# CONTROL_485.net
KiCad netlist of a schematic drawn in Altium Designer
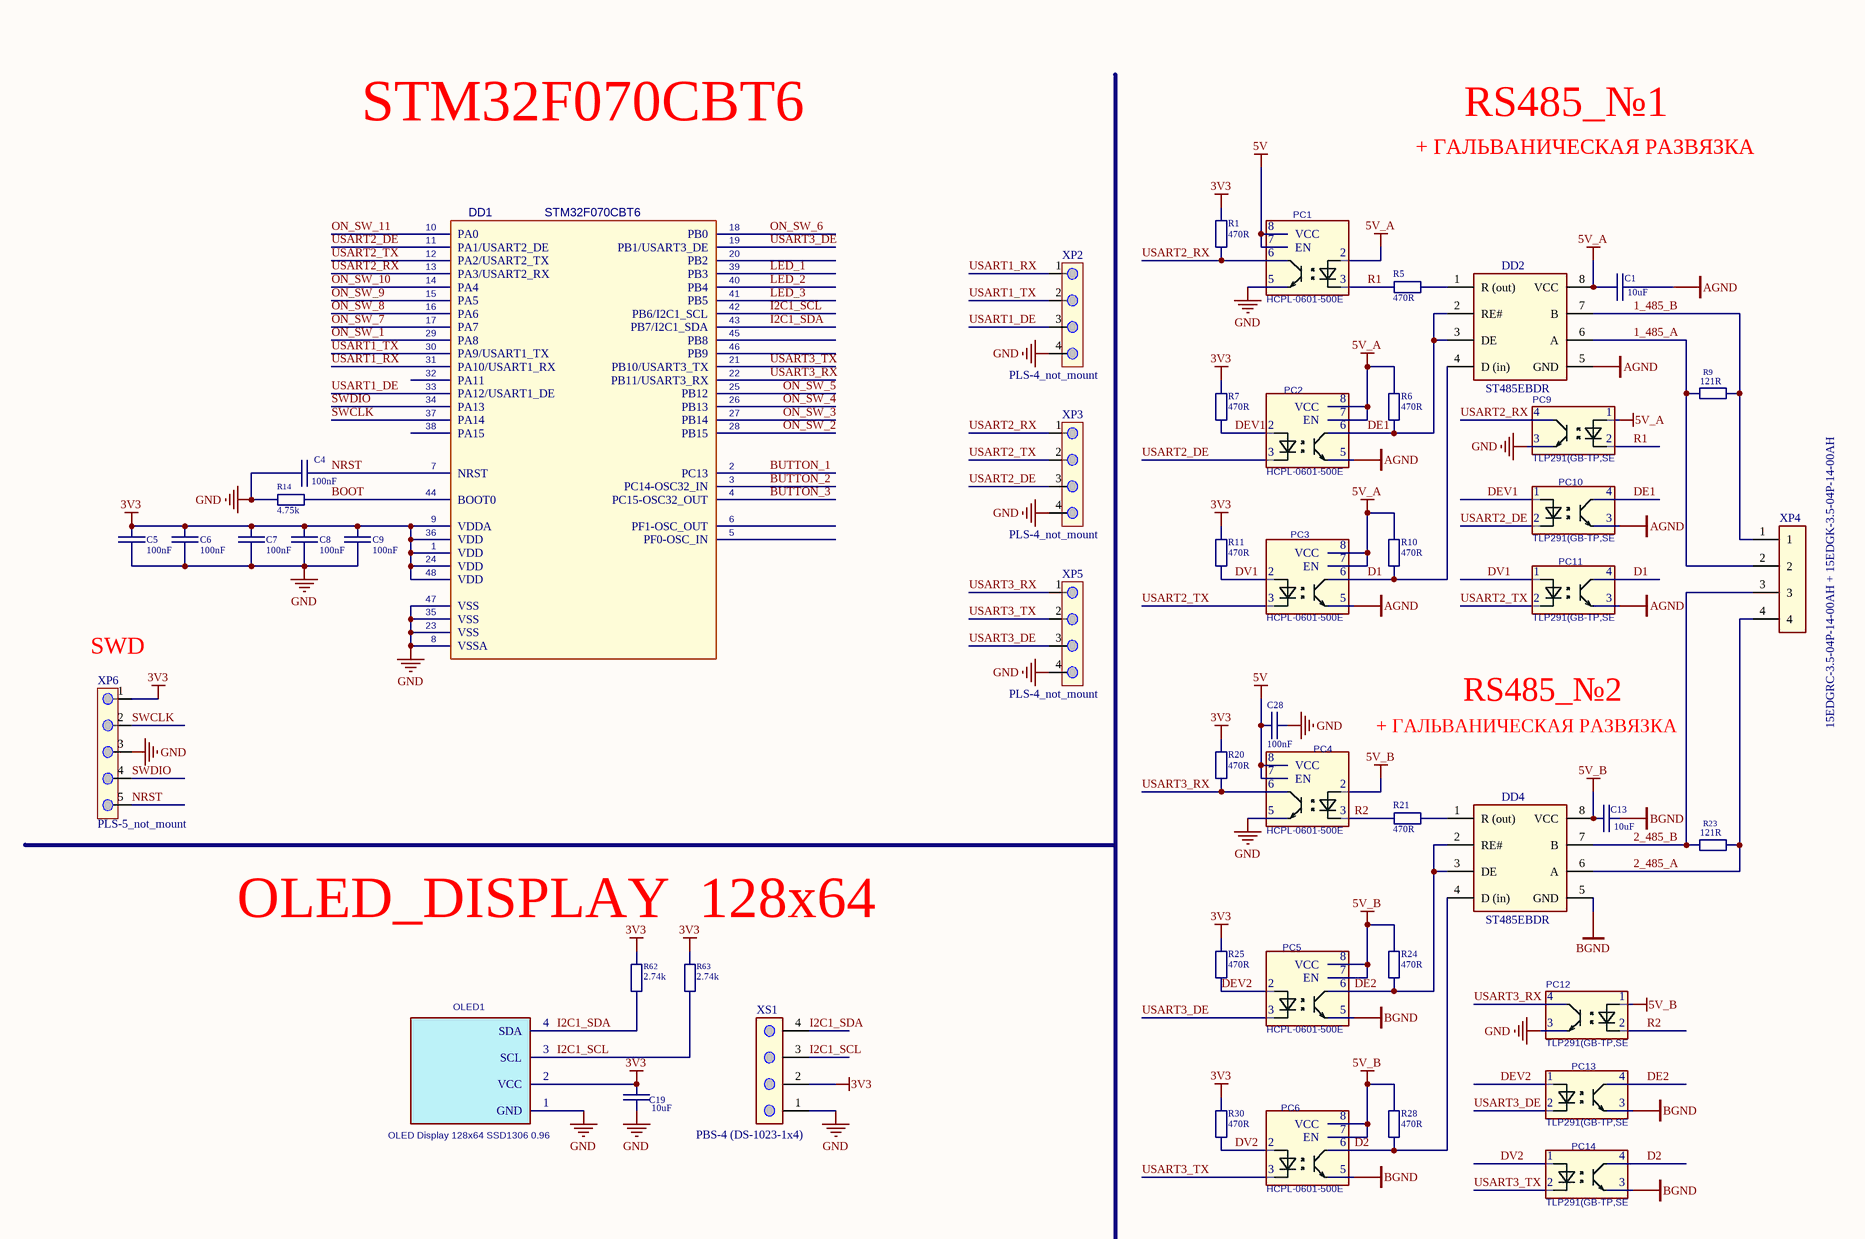
[diagram p0: CONTROL_485.SchDoc, top left]
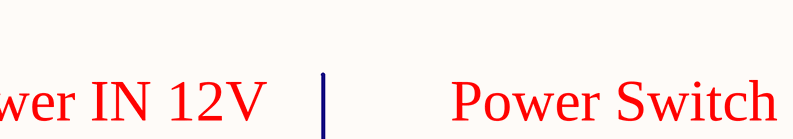
[diagram p1: CONTROL_485.SchDoc, top right]
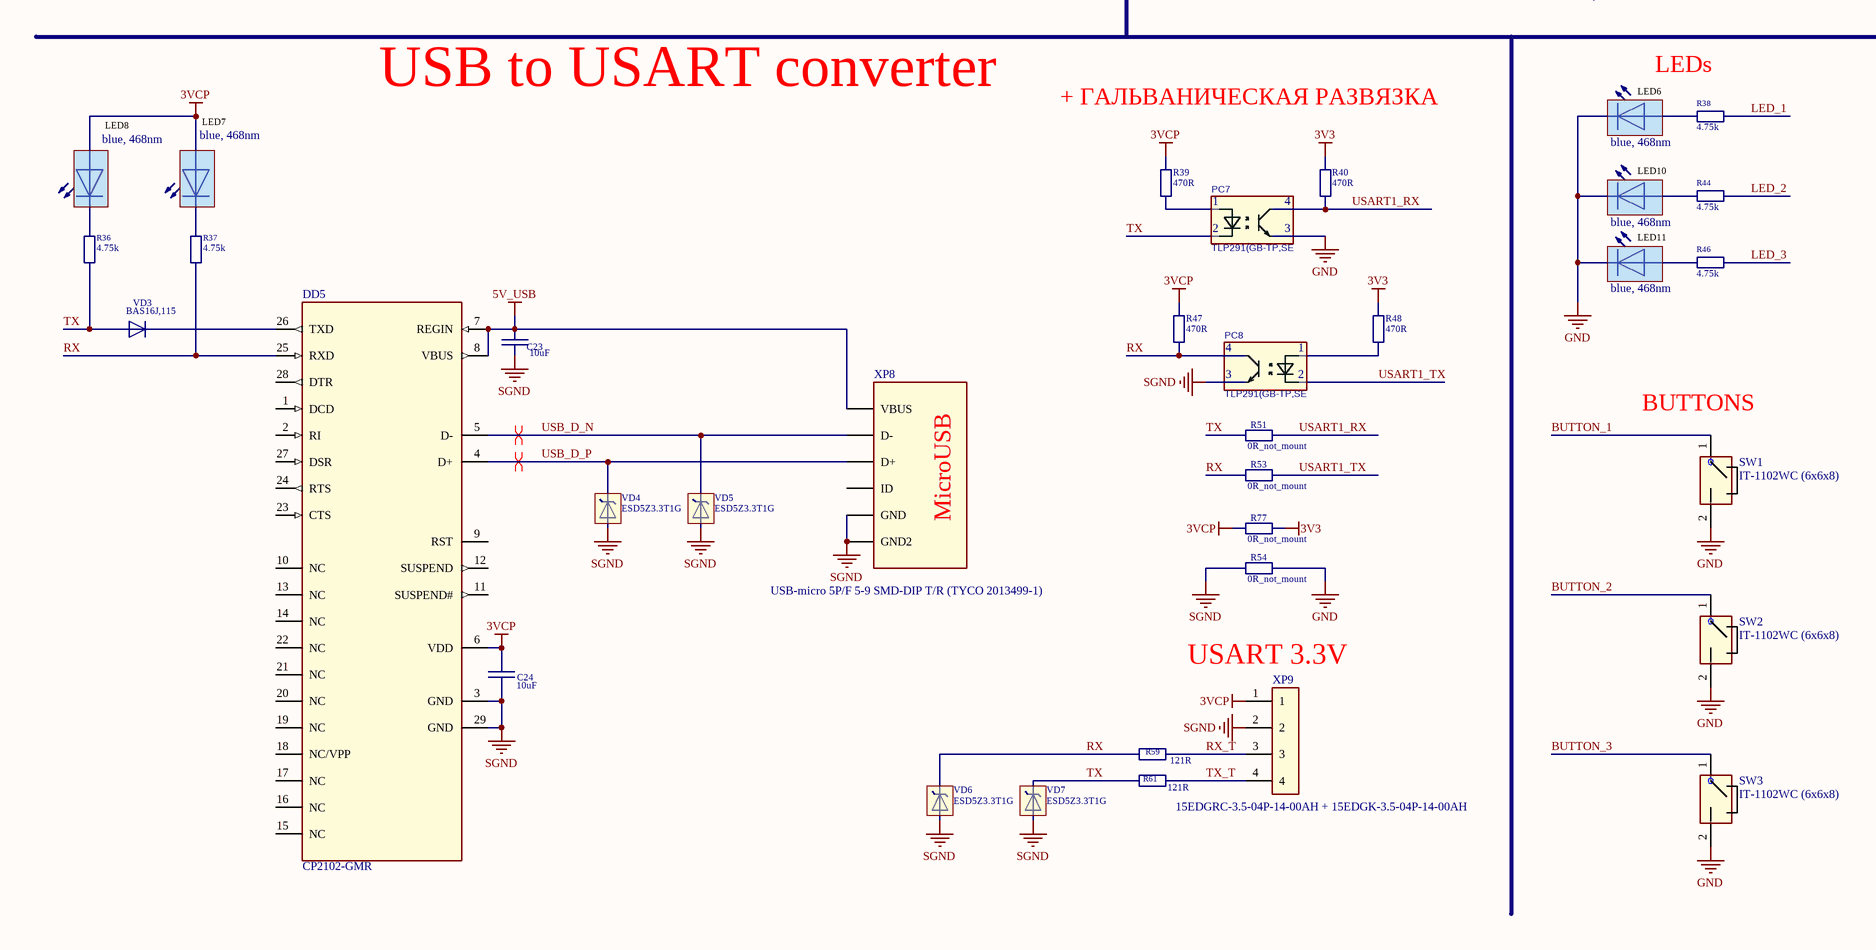
[diagram p2: CONTROL_485.SchDoc, bottom left]
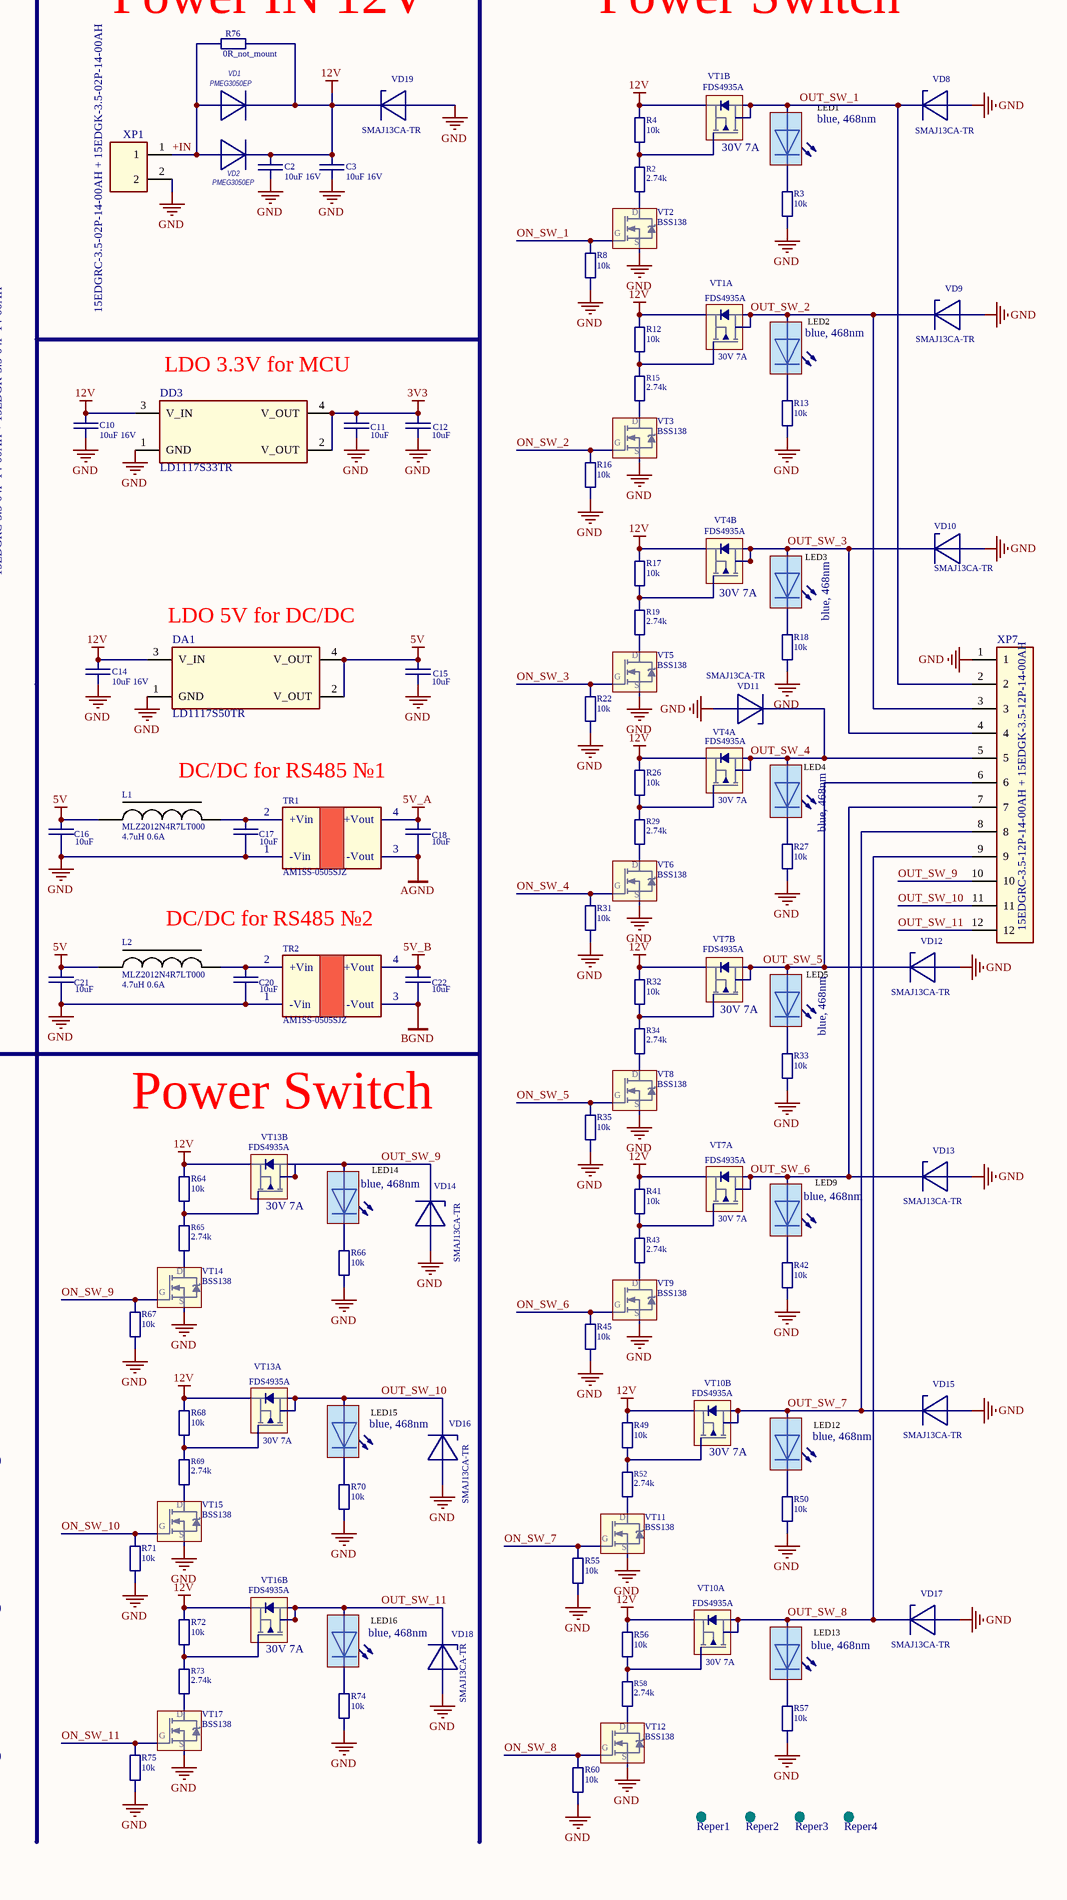
[diagram p3: CONTROL_485.SchDoc, bottom right]

(export (version "E")
  (design (tool "Eeschema 10.0.6"))
  (components
    (comp (ref "C1")
      (value "C0805, 10uF, 10V, X5R")
      (footprint "C0805")
      (fields (field (name "CAPACITANCE") "10uF"))
      (libsource (lib "CAPACITORS") (part "C0805, 10uF, 10V, X5R"))
    )
    (comp (ref "C2")
      (value "C0805, 10uF, 16V, X5R")
      (footprint "C0805")
      (fields (field (name "CAPACITANCE") "10uF 16V"))
      (libsource (lib "*") (part "C0805, 10uF, 16V, X5R"))
    )
    (comp (ref "C3")
      (value "C0805, 10uF, 16V, X5R")
      (footprint "C0805")
      (fields (field (name "CAPACITANCE") "10uF 16V"))
      (libsource (lib "*") (part "C0805, 10uF, 16V, X5R"))
    )
    (comp (ref "C4")
      (value "C0603, 100nF 50V")
      (footprint "C0603")
      (fields (field (name "CAPACITANCE") "100nF"))
      (libsource (lib "CAPACITORS") (part "C0603, 100nF 50V"))
    )
    (comp (ref "C5")
      (value "C0603, 100nF 50V")
      (footprint "C0603")
      (fields (field (name "CAPACITANCE") "100nF"))
      (libsource (lib "CAPACITORS") (part "C0603, 100nF 50V"))
    )
    (comp (ref "C6")
      (value "C0603, 100nF 50V")
      (footprint "C0603")
      (fields (field (name "CAPACITANCE") "100nF"))
      (libsource (lib "CAPACITORS") (part "C0603, 100nF 50V"))
    )
    (comp (ref "C7")
      (value "C0603, 100nF 50V")
      (footprint "C0603")
      (fields (field (name "CAPACITANCE") "100nF"))
      (libsource (lib "CAPACITORS") (part "C0603, 100nF 50V"))
    )
    (comp (ref "C8")
      (value "C0603, 100nF 50V")
      (footprint "C0603")
      (fields (field (name "CAPACITANCE") "100nF"))
      (libsource (lib "CAPACITORS") (part "C0603, 100nF 50V"))
    )
    (comp (ref "C9")
      (value "C0603, 100nF 50V")
      (footprint "C0603")
      (fields (field (name "CAPACITANCE") "100nF"))
      (libsource (lib "CAPACITORS") (part "C0603, 100nF 50V"))
    )
    (comp (ref "C10")
      (value "C0805, 10uF, 16V, X5R")
      (footprint "C0805")
      (fields (field (name "CAPACITANCE") "10uF 16V"))
      (libsource (lib "*") (part "C0805, 10uF, 16V, X5R"))
    )
    (comp (ref "C11")
      (value "C0805, 10uF, 10V, X5R")
      (footprint "C0805")
      (fields (field (name "CAPACITANCE") "10uF"))
      (libsource (lib "CAPACITORS") (part "C0805, 10uF, 10V, X5R"))
    )
    (comp (ref "C12")
      (value "C0805, 10uF, 10V, X5R")
      (footprint "C0805")
      (fields (field (name "CAPACITANCE") "10uF"))
      (libsource (lib "CAPACITORS") (part "C0805, 10uF, 10V, X5R"))
    )
    (comp (ref "C13")
      (value "C0805, 10uF, 10V, X5R")
      (footprint "C0805")
      (fields (field (name "CAPACITANCE") "10uF"))
      (libsource (lib "CAPACITORS") (part "C0805, 10uF, 10V, X5R"))
    )
    (comp (ref "C14")
      (value "C0805, 10uF, 16V, X5R")
      (footprint "C0805")
      (fields (field (name "CAPACITANCE") "10uF 16V"))
      (libsource (lib "*") (part "C0805, 10uF, 16V, X5R"))
    )
    (comp (ref "C15")
      (value "C0805, 10uF, 10V, X5R")
      (footprint "C0805")
      (fields (field (name "CAPACITANCE") "10uF"))
      (libsource (lib "CAPACITORS") (part "C0805, 10uF, 10V, X5R"))
    )
    (comp (ref "C16")
      (value "C0805, 10uF, 10V, X5R")
      (footprint "C0805")
      (fields (field (name "CAPACITANCE") "10uF"))
      (libsource (lib "CAPACITORS") (part "C0805, 10uF, 10V, X5R"))
    )
    (comp (ref "C17")
      (value "C0805, 10uF, 10V, X5R")
      (footprint "C0805")
      (fields (field (name "CAPACITANCE") "10uF"))
      (libsource (lib "CAPACITORS") (part "C0805, 10uF, 10V, X5R"))
    )
    (comp (ref "C18")
      (value "C0805, 10uF, 10V, X5R")
      (footprint "C0805")
      (fields (field (name "CAPACITANCE") "10uF"))
      (libsource (lib "CAPACITORS") (part "C0805, 10uF, 10V, X5R"))
    )
    (comp (ref "C19")
      (value "C0805, 10uF, 10V, X5R")
      (footprint "C0805")
      (fields (field (name "CAPACITANCE") "10uF"))
      (libsource (lib "CAPACITORS") (part "C0805, 10uF, 10V, X5R"))
    )
    (comp (ref "C20")
      (value "C0805, 10uF, 10V, X5R")
      (footprint "C0805")
      (fields (field (name "CAPACITANCE") "10uF"))
      (libsource (lib "CAPACITORS") (part "C0805, 10uF, 10V, X5R"))
    )
    (comp (ref "C21")
      (value "C0805, 10uF, 10V, X5R")
      (footprint "C0805")
      (fields (field (name "CAPACITANCE") "10uF"))
      (libsource (lib "CAPACITORS") (part "C0805, 10uF, 10V, X5R"))
    )
    (comp (ref "C22")
      (value "C0805, 10uF, 10V, X5R")
      (footprint "C0805")
      (fields (field (name "CAPACITANCE") "10uF"))
      (libsource (lib "CAPACITORS") (part "C0805, 10uF, 10V, X5R"))
    )
    (comp (ref "C23")
      (value "C0805, 10uF, 10V, X5R")
      (footprint "C0805")
      (fields (field (name "CAPACITANCE") "10uF"))
      (libsource (lib "CAPACITORS") (part "C0805, 10uF, 10V, X5R"))
    )
    (comp (ref "C24")
      (value "C0805, 10uF, 10V, X5R")
      (footprint "C0805")
      (fields (field (name "CAPACITANCE") "10uF"))
      (libsource (lib "CAPACITORS") (part "C0805, 10uF, 10V, X5R"))
    )
    (comp (ref "C28")
      (value "C0603, 100nF 50V")
      (footprint "C0603")
      (fields (field (name "CAPACITANCE") "100nF"))
      (libsource (lib "CAPACITORS") (part "C0603, 100nF 50V"))
    )
    (comp (ref "DA1")
      (value "LD1117S50TR")
      (footprint "SOT223_N")
      (description "IC REG LDO 0.8A 5V SOT223-4")
      (fields
        (field (name "MANUFACTURER PART NUMBER") "NX1117C33Z,115")
        (field (name "MANUFACTURER") "NXP Semiconductors")
      )
      (libsource (lib "DIGITAL and ANALOG ICs") (part "LD1117S50TR"))
    )
    (comp (ref "DD1")
      (value "STM32F070CBT6")
      (footprint "LQFP48_L")
      (description "ARM® Cortex®-M0 STM32F0 Microcontroller IC 32-Bit 48MHz 128KB (128K x 8) FLASH 48-LQFP (7x7)")
      (libsource (lib "*") (part "STM32F070CBT6"))
    )
    (comp (ref "DD2")
      (value "ST485EBDR")
      (footprint "SO-8_L")
      (description "Transceiver RS485, 8-SOIC")
      (libsource (lib "*") (part "ST485EBDR"))
    )
    (comp (ref "DD3")
      (value "LD1117S33TR")
      (footprint "SOT223_N")
      (description "IC REG LDO 0.8A 3.3V SOT223-4")
      (fields
        (field (name "MANUFACTURER PART NUMBER") "NX1117C33Z,115")
        (field (name "MANUFACTURER") "NXP Semiconductors")
      )
      (libsource (lib "DIGITAL and ANALOG ICs") (part "LD1117S33TR"))
    )
    (comp (ref "DD4")
      (value "ST485EBDR")
      (footprint "SO-8_L")
      (description "Transceiver RS485, 8-SOIC")
      (libsource (lib "*") (part "ST485EBDR"))
    )
    (comp (ref "DD5")
      (value "CP2102-GMR")
      (footprint "QFN28")
      (description "IC USB-TO-UART BRIDGE 28VQFN")
      (libsource (lib "DIGITAL and ANALOG ICs") (part "CP2102-GMR"))
    )
    (comp (ref "L1")
      (value "MLZ2012N4R7LT000")
      (footprint "L0805")
      (description "4.7µH Shielded Multilayer Inductor 600mA 180mOhm 0805 (2012 Metric)")
      (fields (field (name "ALTIUM_UNNAMED_1") "4.7uH 0.6A"))
      (libsource (lib "INDUCTORS") (part "MLZ2012N4R7LT000"))
    )
    (comp (ref "L2")
      (value "MLZ2012N4R7LT000")
      (footprint "L0805")
      (description "4.7µH Shielded Multilayer Inductor 600mA 180mOhm 0805 (2012 Metric)")
      (fields (field (name "ALTIUM_UNNAMED_1") "4.7uH 0.6A"))
      (libsource (lib "INDUCTORS") (part "MLZ2012N4R7LT000"))
    )
    (comp (ref "LED1")
      (value "FYLS-0805BUBC")
      (footprint "LED_0805_B")
      (description "LED, blue, 0805")
      (fields (field (name "ALTIUM_UNNAMED_1") "blue, 468nm"))
      (libsource (lib "AltiumDesignLibrary") (part "FYLS-0805BUBC"))
    )
    (comp (ref "LED2")
      (value "FYLS-0805BUBC")
      (footprint "LED_0805_B")
      (description "LED, blue, 0805")
      (fields (field (name "ALTIUM_UNNAMED_1") "blue, 468nm"))
      (libsource (lib "AltiumDesignLibrary") (part "FYLS-0805BUBC"))
    )
    (comp (ref "LED3")
      (value "FYLS-0805BUBC")
      (footprint "LED_0805_B")
      (description "LED, blue, 0805")
      (fields (field (name "ALTIUM_UNNAMED_1") "blue, 468nm"))
      (libsource (lib "AltiumDesignLibrary") (part "FYLS-0805BUBC"))
    )
    (comp (ref "LED4")
      (value "FYLS-0805BUBC")
      (footprint "LED_0805_B")
      (description "LED, blue, 0805")
      (fields (field (name "ALTIUM_UNNAMED_1") "blue, 468nm"))
      (libsource (lib "AltiumDesignLibrary") (part "FYLS-0805BUBC"))
    )
    (comp (ref "LED5")
      (value "FYLS-0805BUBC")
      (footprint "LED_0805_B")
      (description "LED, blue, 0805")
      (fields (field (name "ALTIUM_UNNAMED_1") "blue, 468nm"))
      (libsource (lib "AltiumDesignLibrary") (part "FYLS-0805BUBC"))
    )
    (comp (ref "LED6")
      (value "FYLS-0805BUBC")
      (footprint "LED_0805_B")
      (description "LED, blue, 0805")
      (fields (field (name "ALTIUM_UNNAMED_1") "blue, 468nm"))
      (libsource (lib "AltiumDesignLibrary") (part "FYLS-0805BUBC"))
    )
    (comp (ref "LED7")
      (value "FYLS-0805BUBC")
      (footprint "LED_0805_B")
      (description "LED, blue, 0805")
      (fields (field (name "ALTIUM_UNNAMED_1") "blue, 468nm"))
      (libsource (lib "") (part "FYLS-0805BUBC_1"))
    )
    (comp (ref "LED8")
      (value "FYLS-0805BUBC")
      (footprint "LED_0805_B")
      (description "LED, blue, 0805")
      (fields (field (name "ALTIUM_UNNAMED_1") "blue, 468nm"))
      (libsource (lib "") (part "FYLS-0805BUBC_1"))
    )
    (comp (ref "LED9")
      (value "FYLS-0805BUBC")
      (footprint "LED_0805_B")
      (description "LED, blue, 0805")
      (fields (field (name "ALTIUM_UNNAMED_1") "blue, 468nm"))
      (libsource (lib "AltiumDesignLibrary") (part "FYLS-0805BUBC"))
    )
    (comp (ref "LED10")
      (value "FYLS-0805BUBC")
      (footprint "LED_0805_B")
      (description "LED, blue, 0805")
      (fields (field (name "ALTIUM_UNNAMED_1") "blue, 468nm"))
      (libsource (lib "AltiumDesignLibrary") (part "FYLS-0805BUBC"))
    )
    (comp (ref "LED11")
      (value "FYLS-0805BUBC")
      (footprint "LED_0805_B")
      (description "LED, blue, 0805")
      (fields (field (name "ALTIUM_UNNAMED_1") "blue, 468nm"))
      (libsource (lib "AltiumDesignLibrary") (part "FYLS-0805BUBC"))
    )
    (comp (ref "LED12")
      (value "FYLS-0805BUBC")
      (footprint "LED_0805_B")
      (description "LED, blue, 0805")
      (fields (field (name "ALTIUM_UNNAMED_1") "blue, 468nm"))
      (libsource (lib "AltiumDesignLibrary") (part "FYLS-0805BUBC"))
    )
    (comp (ref "LED13")
      (value "FYLS-0805BUBC")
      (footprint "LED_0805_B")
      (description "LED, blue, 0805")
      (fields (field (name "ALTIUM_UNNAMED_1") "blue, 468nm"))
      (libsource (lib "AltiumDesignLibrary") (part "FYLS-0805BUBC"))
    )
    (comp (ref "LED14")
      (value "FYLS-0805BUBC")
      (footprint "LED_0805_B")
      (description "LED, blue, 0805")
      (fields (field (name "ALTIUM_UNNAMED_1") "blue, 468nm"))
      (libsource (lib "AltiumDesignLibrary") (part "FYLS-0805BUBC"))
    )
    (comp (ref "LED15")
      (value "FYLS-0805BUBC")
      (footprint "LED_0805_B")
      (description "LED, blue, 0805")
      (fields (field (name "ALTIUM_UNNAMED_1") "blue, 468nm"))
      (libsource (lib "AltiumDesignLibrary") (part "FYLS-0805BUBC"))
    )
    (comp (ref "LED16")
      (value "FYLS-0805BUBC")
      (footprint "LED_0805_B")
      (description "LED, blue, 0805")
      (fields (field (name "ALTIUM_UNNAMED_1") "blue, 468nm"))
      (libsource (lib "AltiumDesignLibrary") (part "FYLS-0805BUBC"))
    )
    (comp (ref "OLED1")
      (value "OLED Display 128x64 SSD1306 0.96")
      (footprint "OLED Display 128x64 SSD1306 0.96")
      (libsource (lib "LED") (part "OLED Display 128x64 SSD1306 0.96"))
    )
    (comp (ref "PC1")
      (value "HCPL-0601-500E")
      (footprint "SO-8_HCPL")
      (description "OPTOISO 3.75KV OPN COLLECTOR 8SO")
      (libsource (lib "") (part "HCPL-0601-500E_1"))
    )
    (comp (ref "PC2")
      (value "HCPL-0601-500E")
      (footprint "SO-8_HCPL")
      (description "OPTOISO 3.75KV OPN COLLECTOR 8SO")
      (libsource (lib "LED") (part "HCPL-0601-500E"))
    )
    (comp (ref "PC3")
      (value "HCPL-0601-500E")
      (footprint "SO-8_HCPL")
      (description "OPTOISO 3.75KV OPN COLLECTOR 8SO")
      (libsource (lib "LED") (part "HCPL-0601-500E"))
    )
    (comp (ref "PC4")
      (value "HCPL-0601-500E")
      (footprint "SO-8_HCPL")
      (description "OPTOISO 3.75KV OPN COLLECTOR 8SO")
      (libsource (lib "") (part "HCPL-0601-500E_1"))
    )
    (comp (ref "PC5")
      (value "HCPL-0601-500E")
      (footprint "SO-8_HCPL")
      (description "OPTOISO 3.75KV OPN COLLECTOR 8SO")
      (libsource (lib "LED") (part "HCPL-0601-500E"))
    )
    (comp (ref "PC6")
      (value "HCPL-0601-500E")
      (footprint "SO-8_HCPL")
      (description "OPTOISO 3.75KV OPN COLLECTOR 8SO")
      (libsource (lib "LED") (part "HCPL-0601-500E"))
    )
    (comp (ref "PC7")
      (value "TLP291(GB-TP,SE")
      (footprint "TLP292")
      (description "Photocoupler TLP291")
      (libsource (lib "*") (part "TLP291(GB-TP,SE"))
    )
    (comp (ref "PC8")
      (value "TLP291(GB-TP,SE")
      (footprint "TLP292")
      (description "Photocoupler TLP291")
      (libsource (lib "") (part "TLP291(GB-TP,SE_1"))
    )
    (comp (ref "PC9")
      (value "TLP291(GB-TP,SE")
      (footprint "TLP292")
      (description "Photocoupler TLP291")
      (libsource (lib "") (part "TLP291(GB-TP,SE_1"))
    )
    (comp (ref "PC10")
      (value "TLP291(GB-TP,SE")
      (footprint "TLP292")
      (description "Photocoupler TLP291")
      (libsource (lib "LED") (part "TLP291(GB-TP,SE"))
    )
    (comp (ref "PC11")
      (value "TLP291(GB-TP,SE")
      (footprint "TLP292")
      (description "Photocoupler TLP291")
      (libsource (lib "LED") (part "TLP291(GB-TP,SE"))
    )
    (comp (ref "PC12")
      (value "TLP291(GB-TP,SE")
      (footprint "TLP292")
      (description "Photocoupler TLP291")
      (libsource (lib "") (part "TLP291(GB-TP,SE_1"))
    )
    (comp (ref "PC13")
      (value "TLP291(GB-TP,SE")
      (footprint "TLP292")
      (description "Photocoupler TLP291")
      (libsource (lib "LED") (part "TLP291(GB-TP,SE"))
    )
    (comp (ref "PC14")
      (value "TLP291(GB-TP,SE")
      (footprint "TLP292")
      (description "Photocoupler TLP291")
      (libsource (lib "LED") (part "TLP291(GB-TP,SE"))
    )
    (comp (ref "R1")
      (value "R0603, 470R 1%")
      (footprint "R0603")
      (fields (field (name "ALTIUM_UNNAMED_1") "470R"))
      (libsource (lib "RESISTOR") (part "R0603, 470R 1%"))
    )
    (comp (ref "R2")
      (value "R0603, 2.74k 1%")
      (footprint "R0603")
      (fields (field (name "RESISTANCE") "2.74k"))
      (libsource (lib "RESISTOR") (part "R0603, 2.74k 1%"))
    )
    (comp (ref "R3")
      (value "R0603, 10k 1%")
      (footprint "R0603")
      (fields (field (name "RESISTANCE") "10k"))
      (libsource (lib "*") (part "R0603, 10k 1%"))
    )
    (comp (ref "R4")
      (value "R0603, 10k 1%")
      (footprint "R0603")
      (fields (field (name "RESISTANCE") "10k"))
      (libsource (lib "*") (part "R0603, 10k 1%"))
    )
    (comp (ref "R5")
      (value "R0603, 470R 1%")
      (footprint "R0603")
      (fields (field (name "ALTIUM_UNNAMED_1") "470R"))
      (libsource (lib "RESISTOR") (part "R0603, 470R 1%"))
    )
    (comp (ref "R6")
      (value "R0603, 470R 1%")
      (footprint "R0603")
      (fields (field (name "ALTIUM_UNNAMED_1") "470R"))
      (libsource (lib "RESISTOR") (part "R0603, 470R 1%"))
    )
    (comp (ref "R7")
      (value "R0603, 470R 1%")
      (footprint "R0603")
      (fields (field (name "ALTIUM_UNNAMED_1") "470R"))
      (libsource (lib "RESISTOR") (part "R0603, 470R 1%"))
    )
    (comp (ref "R8")
      (value "R0603, 10k 1%")
      (footprint "R0603")
      (fields (field (name "RESISTANCE") "10k"))
      (libsource (lib "*") (part "R0603, 10k 1%"))
    )
    (comp (ref "R9")
      (value "R0603, 121R 1%")
      (footprint "R0603")
      (fields (field (name "RESISTANCE") "121R"))
      (libsource (lib "MAIN_BOARD_V3") (part "R0603, 121R 1%"))
    )
    (comp (ref "R10")
      (value "R0603, 470R 1%")
      (footprint "R0603")
      (fields (field (name "ALTIUM_UNNAMED_1") "470R"))
      (libsource (lib "RESISTOR") (part "R0603, 470R 1%"))
    )
    (comp (ref "R11")
      (value "R0603, 470R 1%")
      (footprint "R0603")
      (fields (field (name "ALTIUM_UNNAMED_1") "470R"))
      (libsource (lib "RESISTOR") (part "R0603, 470R 1%"))
    )
    (comp (ref "R12")
      (value "R0603, 10k 1%")
      (footprint "R0603")
      (fields (field (name "RESISTANCE") "10k"))
      (libsource (lib "RESISTOR") (part "R0603, 10k 1%"))
    )
    (comp (ref "R13")
      (value "R0603, 10k 1%")
      (footprint "R0603")
      (fields (field (name "RESISTANCE") "10k"))
      (libsource (lib "*") (part "R0603, 10k 1%"))
    )
    (comp (ref "R14")
      (value "R0603, 4.75k 1%")
      (footprint "R0603")
      (fields (field (name "RESISTANCE") "4.75k"))
      (libsource (lib "RESISTOR") (part "R0603, 4.75k 1%"))
    )
    (comp (ref "R15")
      (value "R0603, 2.74k 1%")
      (footprint "R0603")
      (fields (field (name "RESISTANCE") "2.74k"))
      (libsource (lib "RESISTOR") (part "R0603, 2.74k 1%"))
    )
    (comp (ref "R16")
      (value "R0603, 10k 1%")
      (footprint "R0603")
      (fields (field (name "RESISTANCE") "10k"))
      (libsource (lib "RESISTOR") (part "R0603, 10k 1%"))
    )
    (comp (ref "R17")
      (value "R0603, 10k 1%")
      (footprint "R0603")
      (fields (field (name "RESISTANCE") "10k"))
      (libsource (lib "RESISTOR") (part "R0603, 10k 1%"))
    )
    (comp (ref "R18")
      (value "R0603, 10k 1%")
      (footprint "R0603")
      (fields (field (name "RESISTANCE") "10k"))
      (libsource (lib "*") (part "R0603, 10k 1%"))
    )
    (comp (ref "R19")
      (value "R0603, 2.74k 1%")
      (footprint "R0603")
      (fields (field (name "RESISTANCE") "2.74k"))
      (libsource (lib "RESISTOR") (part "R0603, 2.74k 1%"))
    )
    (comp (ref "R20")
      (value "R0603, 470R 1%")
      (footprint "R0603")
      (fields (field (name "ALTIUM_UNNAMED_1") "470R"))
      (libsource (lib "RESISTOR") (part "R0603, 470R 1%"))
    )
    (comp (ref "R21")
      (value "R0603, 470R 1%")
      (footprint "R0603")
      (fields (field (name "ALTIUM_UNNAMED_1") "470R"))
      (libsource (lib "RESISTOR") (part "R0603, 470R 1%"))
    )
    (comp (ref "R22")
      (value "R0603, 10k 1%")
      (footprint "R0603")
      (fields (field (name "RESISTANCE") "10k"))
      (libsource (lib "RESISTOR") (part "R0603, 10k 1%"))
    )
    (comp (ref "R23")
      (value "R0603, 121R 1%")
      (footprint "R0603")
      (fields (field (name "RESISTANCE") "121R"))
      (libsource (lib "MAIN_BOARD_V3") (part "R0603, 121R 1%"))
    )
    (comp (ref "R24")
      (value "R0603, 470R 1%")
      (footprint "R0603")
      (fields (field (name "ALTIUM_UNNAMED_1") "470R"))
      (libsource (lib "RESISTOR") (part "R0603, 470R 1%"))
    )
    (comp (ref "R25")
      (value "R0603, 470R 1%")
      (footprint "R0603")
      (fields (field (name "ALTIUM_UNNAMED_1") "470R"))
      (libsource (lib "RESISTOR") (part "R0603, 470R 1%"))
    )
    (comp (ref "R26")
      (value "R0603, 10k 1%")
      (footprint "R0603")
      (fields (field (name "RESISTANCE") "10k"))
      (libsource (lib "RESISTOR") (part "R0603, 10k 1%"))
    )
    (comp (ref "R27")
      (value "R0603, 10k 1%")
      (footprint "R0603")
      (fields (field (name "RESISTANCE") "10k"))
      (libsource (lib "*") (part "R0603, 10k 1%"))
    )
    (comp (ref "R28")
      (value "R0603, 470R 1%")
      (footprint "R0603")
      (fields (field (name "ALTIUM_UNNAMED_1") "470R"))
      (libsource (lib "RESISTOR") (part "R0603, 470R 1%"))
    )
    (comp (ref "R29")
      (value "R0603, 2.74k 1%")
      (footprint "R0603")
      (fields (field (name "RESISTANCE") "2.74k"))
      (libsource (lib "RESISTOR") (part "R0603, 2.74k 1%"))
    )
    (comp (ref "R30")
      (value "R0603, 470R 1%")
      (footprint "R0603")
      (fields (field (name "ALTIUM_UNNAMED_1") "470R"))
      (libsource (lib "RESISTOR") (part "R0603, 470R 1%"))
    )
    (comp (ref "R31")
      (value "R0603, 10k 1%")
      (footprint "R0603")
      (fields (field (name "RESISTANCE") "10k"))
      (libsource (lib "RESISTOR") (part "R0603, 10k 1%"))
    )
    (comp (ref "R32")
      (value "R0603, 10k 1%")
      (footprint "R0603")
      (fields (field (name "RESISTANCE") "10k"))
      (libsource (lib "RESISTOR") (part "R0603, 10k 1%"))
    )
    (comp (ref "R33")
      (value "R0603, 10k 1%")
      (footprint "R0603")
      (fields (field (name "RESISTANCE") "10k"))
      (libsource (lib "*") (part "R0603, 10k 1%"))
    )
    (comp (ref "R34")
      (value "R0603, 2.74k 1%")
      (footprint "R0603")
      (fields (field (name "RESISTANCE") "2.74k"))
      (libsource (lib "RESISTOR") (part "R0603, 2.74k 1%"))
    )
    (comp (ref "R35")
      (value "R0603, 10k 1%")
      (footprint "R0603")
      (fields (field (name "RESISTANCE") "10k"))
      (libsource (lib "RESISTOR") (part "R0603, 10k 1%"))
    )
    (comp (ref "R36")
      (value "R0603, 4.75k 1%")
      (footprint "R0603")
      (fields (field (name "RESISTANCE") "4.75k"))
      (libsource (lib "RESISTOR") (part "R0603, 4.75k 1%"))
    )
    (comp (ref "R37")
      (value "R0603, 4.75k 1%")
      (footprint "R0603")
      (fields (field (name "RESISTANCE") "4.75k"))
      (libsource (lib "RESISTOR") (part "R0603, 4.75k 1%"))
    )
    (comp (ref "R38")
      (value "R0603, 4.75k 1%")
      (footprint "R0603")
      (fields (field (name "RESISTANCE") "4.75k"))
      (libsource (lib "RESISTOR") (part "R0603, 4.75k 1%"))
    )
    (comp (ref "R39")
      (value "R0603, 470R 1%")
      (footprint "R0603")
      (fields (field (name "ALTIUM_UNNAMED_1") "470R"))
      (libsource (lib "RESISTOR") (part "R0603, 470R 1%"))
    )
    (comp (ref "R40")
      (value "R0603, 470R 1%")
      (footprint "R0603")
      (fields (field (name "ALTIUM_UNNAMED_1") "470R"))
      (libsource (lib "RESISTOR") (part "R0603, 470R 1%"))
    )
    (comp (ref "R41")
      (value "R0603, 10k 1%")
      (footprint "R0603")
      (fields (field (name "RESISTANCE") "10k"))
      (libsource (lib "RESISTOR") (part "R0603, 10k 1%"))
    )
    (comp (ref "R42")
      (value "R0603, 10k 1%")
      (footprint "R0603")
      (fields (field (name "RESISTANCE") "10k"))
      (libsource (lib "*") (part "R0603, 10k 1%"))
    )
    (comp (ref "R43")
      (value "R0603, 2.74k 1%")
      (footprint "R0603")
      (fields (field (name "RESISTANCE") "2.74k"))
      (libsource (lib "RESISTOR") (part "R0603, 2.74k 1%"))
    )
    (comp (ref "R44")
      (value "R0603, 4.75k 1%")
      (footprint "R0603")
      (fields (field (name "RESISTANCE") "4.75k"))
      (libsource (lib "RESISTOR") (part "R0603, 4.75k 1%"))
    )
    (comp (ref "R45")
      (value "R0603, 10k 1%")
      (footprint "R0603")
      (fields (field (name "RESISTANCE") "10k"))
      (libsource (lib "RESISTOR") (part "R0603, 10k 1%"))
    )
    (comp (ref "R46")
      (value "R0603, 4.75k 1%")
      (footprint "R0603")
      (fields (field (name "RESISTANCE") "4.75k"))
      (libsource (lib "RESISTOR") (part "R0603, 4.75k 1%"))
    )
    (comp (ref "R47")
      (value "R0603, 470R 1%")
      (footprint "R0603")
      (fields (field (name "ALTIUM_UNNAMED_1") "470R"))
      (libsource (lib "RESISTOR") (part "R0603, 470R 1%"))
    )
    (comp (ref "R48")
      (value "R0603, 470R 1%")
      (footprint "R0603")
      (fields (field (name "ALTIUM_UNNAMED_1") "470R"))
      (libsource (lib "RESISTOR") (part "R0603, 470R 1%"))
    )
    (comp (ref "R49")
      (value "R0603, 10k 1%")
      (footprint "R0603")
      (fields (field (name "RESISTANCE") "10k"))
      (libsource (lib "RESISTOR") (part "R0603, 10k 1%"))
    )
    (comp (ref "R50")
      (value "R0603, 10k 1%")
      (footprint "R0603")
      (fields (field (name "RESISTANCE") "10k"))
      (libsource (lib "*") (part "R0603, 10k 1%"))
    )
    (comp (ref "R51")
      (value "R0805, 0R_not_mount")
      (footprint "R0805")
      (fields (field (name "TOLERANCE") "±1%") (field (name "ALTIUM_UNNAMED_1") "0R_not_mount"))
      (libsource (lib "*") (part "R0805, 0R_not_mount"))
    )
    (comp (ref "R52")
      (value "R0603, 2.74k 1%")
      (footprint "R0603")
      (fields (field (name "RESISTANCE") "2.74k"))
      (libsource (lib "RESISTOR") (part "R0603, 2.74k 1%"))
    )
    (comp (ref "R53")
      (value "R0805, 0R_not_mount")
      (footprint "R0805")
      (fields (field (name "TOLERANCE") "±1%") (field (name "ALTIUM_UNNAMED_1") "0R_not_mount"))
      (libsource (lib "*") (part "R0805, 0R_not_mount"))
    )
    (comp (ref "R54")
      (value "R0805, 0R_not_mount")
      (footprint "R0805")
      (fields (field (name "TOLERANCE") "±1%") (field (name "ALTIUM_UNNAMED_1") "0R_not_mount"))
      (libsource (lib "*") (part "R0805, 0R_not_mount"))
    )
    (comp (ref "R55")
      (value "R0603, 10k 1%")
      (footprint "R0603")
      (fields (field (name "RESISTANCE") "10k"))
      (libsource (lib "RESISTOR") (part "R0603, 10k 1%"))
    )
    (comp (ref "R56")
      (value "R0603, 10k 1%")
      (footprint "R0603")
      (fields (field (name "RESISTANCE") "10k"))
      (libsource (lib "RESISTOR") (part "R0603, 10k 1%"))
    )
    (comp (ref "R57")
      (value "R0603, 10k 1%")
      (footprint "R0603")
      (fields (field (name "RESISTANCE") "10k"))
      (libsource (lib "*") (part "R0603, 10k 1%"))
    )
    (comp (ref "R58")
      (value "R0603, 2.74k 1%")
      (footprint "R0603")
      (fields (field (name "RESISTANCE") "2.74k"))
      (libsource (lib "RESISTOR") (part "R0603, 2.74k 1%"))
    )
    (comp (ref "R59")
      (value "R0603, 121R 1%")
      (footprint "R0603")
      (fields (field (name "RESISTANCE") "121R"))
      (libsource (lib "MAIN_BOARD_V3") (part "R0603, 121R 1%"))
    )
    (comp (ref "R60")
      (value "R0603, 10k 1%")
      (footprint "R0603")
      (fields (field (name "RESISTANCE") "10k"))
      (libsource (lib "RESISTOR") (part "R0603, 10k 1%"))
    )
    (comp (ref "R61")
      (value "R0603, 121R 1%")
      (footprint "R0603")
      (fields (field (name "RESISTANCE") "121R"))
      (libsource (lib "MAIN_BOARD_V3") (part "R0603, 121R 1%"))
    )
    (comp (ref "R62")
      (value "R0603, 2.74k 1%")
      (footprint "R0603")
      (fields (field (name "RESISTANCE") "2.74k"))
      (libsource (lib "MAIN_BOARD_V3") (part "R0603, 2.74k 1%"))
    )
    (comp (ref "R63")
      (value "R0603, 2.74k 1%")
      (footprint "R0603")
      (fields (field (name "RESISTANCE") "2.74k"))
      (libsource (lib "MAIN_BOARD_V3") (part "R0603, 2.74k 1%"))
    )
    (comp (ref "R64")
      (value "R0603, 10k 1%")
      (footprint "R0603")
      (fields (field (name "RESISTANCE") "10k"))
      (libsource (lib "RESISTOR") (part "R0603, 10k 1%"))
    )
    (comp (ref "R65")
      (value "R0603, 2.74k 1%")
      (footprint "R0603")
      (fields (field (name "RESISTANCE") "2.74k"))
      (libsource (lib "RESISTOR") (part "R0603, 2.74k 1%"))
    )
    (comp (ref "R66")
      (value "R0603, 10k 1%")
      (footprint "R0603")
      (fields (field (name "RESISTANCE") "10k"))
      (libsource (lib "*") (part "R0603, 10k 1%"))
    )
    (comp (ref "R67")
      (value "R0603, 10k 1%")
      (footprint "R0603")
      (fields (field (name "RESISTANCE") "10k"))
      (libsource (lib "RESISTOR") (part "R0603, 10k 1%"))
    )
    (comp (ref "R68")
      (value "R0603, 10k 1%")
      (footprint "R0603")
      (fields (field (name "RESISTANCE") "10k"))
      (libsource (lib "RESISTOR") (part "R0603, 10k 1%"))
    )
    (comp (ref "R69")
      (value "R0603, 2.74k 1%")
      (footprint "R0603")
      (fields (field (name "RESISTANCE") "2.74k"))
      (libsource (lib "RESISTOR") (part "R0603, 2.74k 1%"))
    )
    (comp (ref "R70")
      (value "R0603, 10k 1%")
      (footprint "R0603")
      (fields (field (name "RESISTANCE") "10k"))
      (libsource (lib "*") (part "R0603, 10k 1%"))
    )
    (comp (ref "R71")
      (value "R0603, 10k 1%")
      (footprint "R0603")
      (fields (field (name "RESISTANCE") "10k"))
      (libsource (lib "RESISTOR") (part "R0603, 10k 1%"))
    )
    (comp (ref "R72")
      (value "R0603, 10k 1%")
      (footprint "R0603")
      (fields (field (name "RESISTANCE") "10k"))
      (libsource (lib "RESISTOR") (part "R0603, 10k 1%"))
    )
    (comp (ref "R73")
      (value "R0603, 2.74k 1%")
      (footprint "R0603")
      (fields (field (name "RESISTANCE") "2.74k"))
      (libsource (lib "RESISTOR") (part "R0603, 2.74k 1%"))
    )
    (comp (ref "R74")
      (value "R0603, 10k 1%")
      (footprint "R0603")
      (fields (field (name "RESISTANCE") "10k"))
      (libsource (lib "*") (part "R0603, 10k 1%"))
    )
    (comp (ref "R75")
      (value "R0603, 10k 1%")
      (footprint "R0603")
      (fields (field (name "RESISTANCE") "10k"))
      (libsource (lib "RESISTOR") (part "R0603, 10k 1%"))
    )
    (comp (ref "R76")
      (value "R0805, 0R_not_mount")
      (footprint "R0805")
      (fields (field (name "TOLERANCE") "±1%") (field (name "ALTIUM_UNNAMED_1") "0R_not_mount"))
      (libsource (lib "*") (part "R0805, 0R_not_mount"))
    )
    (comp (ref "R77")
      (value "R0805, 0R_not_mount")
      (footprint "R0805")
      (fields (field (name "TOLERANCE") "±1%") (field (name "ALTIUM_UNNAMED_1") "0R_not_mount"))
      (libsource (lib "*") (part "R0805, 0R_not_mount"))
    )
    (comp (ref "Reper1")
      (value "Reper")
      (footprint "REPER_1x3")
      (libsource (lib "CONNECTORS") (part "Reper"))
    )
    (comp (ref "Reper2")
      (value "Reper")
      (footprint "REPER_1x3")
      (libsource (lib "CONNECTORS") (part "Reper"))
    )
    (comp (ref "Reper3")
      (value "Reper")
      (footprint "REPER_1x3")
      (libsource (lib "CONNECTORS") (part "Reper"))
    )
    (comp (ref "Reper4")
      (value "Reper")
      (footprint "REPER_1x3")
      (libsource (lib "CONNECTORS") (part "Reper"))
    )
    (comp (ref "SW1")
      (value "IT-1102WC (6x6x8)")
      (footprint "IT-1102WC")
      (description "Horizontal Push Tact Switch")
      (libsource (lib "BUTTONS") (part "IT-1102WC (6x6x8)"))
    )
    (comp (ref "SW2")
      (value "IT-1102WC (6x6x8)")
      (footprint "IT-1102WC")
      (description "Horizontal Push Tact Switch")
      (libsource (lib "BUTTONS") (part "IT-1102WC (6x6x8)"))
    )
    (comp (ref "SW3")
      (value "IT-1102WC (6x6x8)")
      (footprint "IT-1102WC")
      (description "Horizontal Push Tact Switch")
      (libsource (lib "BUTTONS") (part "IT-1102WC (6x6x8)"))
    )
    (comp (ref "TR1")
      (value "AM1SS-0505SJZ")
      (footprint "4-SIP (11.6x6x10.2)")
      (description "Isolated Module DC DC Converter 1 Output 5V    200mA 4.5V - 5.5V Input")
      (libsource (lib "DIGITAL and ANALOG ICs") (part "AM1SS-0505SJZ"))
    )
    (comp (ref "TR2")
      (value "AM1SS-0505SJZ")
      (footprint "4-SIP (11.6x6x10.2)")
      (description "Isolated Module DC DC Converter 1 Output 5V    200mA 4.5V - 5.5V Input")
      (libsource (lib "DIGITAL and ANALOG ICs") (part "AM1SS-0505SJZ"))
    )
    (comp (ref "VD1")
      (value "PMEG3050EP")
      (footprint "SOD128")
      (description "DIODE 5 A 30 V Schottky barrier rectifier")
      (fields
        (field (name "MANUFACTURER PART NUMBER") "PMEG3050EP,115")
        (field (name "MANUFACTURER") "NXP Semiconductors")
      )
      (libsource (lib "DIODES") (part "PMEG3050EP"))
    )
    (comp (ref "VD2")
      (value "PMEG3050EP")
      (footprint "SOD128")
      (description "DIODE 5 A 30 V Schottky barrier rectifier")
      (fields
        (field (name "MANUFACTURER PART NUMBER") "PMEG3050EP,115")
        (field (name "MANUFACTURER") "NXP Semiconductors")
      )
      (libsource (lib "DIODES") (part "PMEG3050EP"))
    )
    (comp (ref "VD3")
      (value "BAS16J,115")
      (footprint "SOD-323")
      (description "Switching Diode 250MA 100V SOD323")
      (libsource (lib "DIODES") (part "BAS16J,115"))
    )
    (comp (ref "VD4")
      (value "ESD5Z3.3T1G")
      (footprint "SOD-523")
      (description "TVS ESD SOD−523")
      (libsource (lib "*") (part "ESD5Z3.3T1G"))
    )
    (comp (ref "VD5")
      (value "ESD5Z3.3T1G")
      (footprint "SOD-523")
      (description "TVS ESD SOD−523")
      (libsource (lib "*") (part "ESD5Z3.3T1G"))
    )
    (comp (ref "VD6")
      (value "ESD5Z3.3T1G")
      (footprint "SOD-523")
      (description "TVS ESD SOD−523")
      (libsource (lib "*") (part "ESD5Z3.3T1G"))
    )
    (comp (ref "VD7")
      (value "ESD5Z3.3T1G")
      (footprint "SOD-523")
      (description "TVS ESD SOD−523")
      (libsource (lib "*") (part "ESD5Z3.3T1G"))
    )
    (comp (ref "VD8")
      (value "SMAJ13CA-TR")
      (footprint "DIODES:SMA")
      (description "TVS DIODE 13V 27.2V SMA")
      (libsource (lib "*") (part "SMAJ13CA-TR"))
    )
    (comp (ref "VD9")
      (value "SMAJ13CA-TR")
      (footprint "DIODES:SMA")
      (description "TVS DIODE 13V 27.2V SMA")
      (libsource (lib "*") (part "SMAJ13CA-TR"))
    )
    (comp (ref "VD10")
      (value "SMAJ13CA-TR")
      (footprint "DIODES:SMA")
      (description "TVS DIODE 13V 27.2V SMA")
      (libsource (lib "*") (part "SMAJ13CA-TR"))
    )
    (comp (ref "VD11")
      (value "SMAJ13CA-TR")
      (footprint "DIODES:SMA")
      (description "TVS DIODE 13V 27.2V SMA")
      (libsource (lib "*") (part "SMAJ13CA-TR"))
    )
    (comp (ref "VD12")
      (value "SMAJ13CA-TR")
      (footprint "DIODES:SMA")
      (description "TVS DIODE 13V 27.2V SMA")
      (libsource (lib "*") (part "SMAJ13CA-TR"))
    )
    (comp (ref "VD13")
      (value "SMAJ13CA-TR")
      (footprint "DIODES:SMA")
      (description "TVS DIODE 13V 27.2V SMA")
      (libsource (lib "*") (part "SMAJ13CA-TR"))
    )
    (comp (ref "VD14")
      (value "SMAJ13CA-TR")
      (footprint "DIODES:SMA")
      (description "TVS DIODE 13V 27.2V SMA")
      (libsource (lib "*") (part "SMAJ13CA-TR"))
    )
    (comp (ref "VD15")
      (value "SMAJ13CA-TR")
      (footprint "DIODES:SMA")
      (description "TVS DIODE 13V 27.2V SMA")
      (libsource (lib "*") (part "SMAJ13CA-TR"))
    )
    (comp (ref "VD16")
      (value "SMAJ13CA-TR")
      (footprint "DIODES:SMA")
      (description "TVS DIODE 13V 27.2V SMA")
      (libsource (lib "*") (part "SMAJ13CA-TR"))
    )
    (comp (ref "VD17")
      (value "SMAJ13CA-TR")
      (footprint "DIODES:SMA")
      (description "TVS DIODE 13V 27.2V SMA")
      (libsource (lib "*") (part "SMAJ13CA-TR"))
    )
    (comp (ref "VD18")
      (value "SMAJ13CA-TR")
      (footprint "DIODES:SMA")
      (description "TVS DIODE 13V 27.2V SMA")
      (libsource (lib "*") (part "SMAJ13CA-TR"))
    )
    (comp (ref "VD19")
      (value "SMAJ13CA-TR")
      (footprint "DIODES:SMA")
      (description "TVS DIODE 13V 27.2V SMA")
      (libsource (lib "*") (part "SMAJ13CA-TR"))
    )
    (comp (ref "VT1")
      (value "FDS4935A")
      (footprint "SO-8_L")
      (description "Mosfet Array 2 P-Channel 30V 7A  8-SO")
      (fields (field (name "ALTIUM_UNNAMED_1") "30V 7A"))
      (libsource (lib "TRANSISTORS") (part "FDS4935A"))
    )
    (comp (ref "VT2")
      (value "BSS138")
      (footprint "SOT-23")
      (description "N-Channel 50V 220mA (Ta) 360mW (Ta) Surface Mount SOT-23-3")
      (fields (field (name "PART NUMBER") "BSS138_ON Semiconductor"))
      (libsource (lib "TRANSISTORS") (part "BSS138"))
    )
    (comp (ref "VT3")
      (value "BSS138")
      (footprint "SOT-23")
      (description "N-Channel 50V 220mA (Ta) 360mW (Ta) Surface Mount SOT-23-3")
      (fields (field (name "PART NUMBER") "BSS138_ON Semiconductor"))
      (libsource (lib "TRANSISTORS") (part "BSS138"))
    )
    (comp (ref "VT4")
      (value "FDS4935A")
      (footprint "SO-8_L")
      (description "Mosfet Array 2 P-Channel 30V 7A  8-SO")
      (fields (field (name "ALTIUM_UNNAMED_1") "30V 7A"))
      (libsource (lib "TRANSISTORS") (part "FDS4935A"))
    )
    (comp (ref "VT5")
      (value "BSS138")
      (footprint "SOT-23")
      (description "N-Channel 50V 220mA (Ta) 360mW (Ta) Surface Mount SOT-23-3")
      (fields (field (name "PART NUMBER") "BSS138_ON Semiconductor"))
      (libsource (lib "TRANSISTORS") (part "BSS138"))
    )
    (comp (ref "VT6")
      (value "BSS138")
      (footprint "SOT-23")
      (description "N-Channel 50V 220mA (Ta) 360mW (Ta) Surface Mount SOT-23-3")
      (fields (field (name "PART NUMBER") "BSS138_ON Semiconductor"))
      (libsource (lib "TRANSISTORS") (part "BSS138"))
    )
    (comp (ref "VT7")
      (value "FDS4935A")
      (footprint "SO-8_L")
      (description "Mosfet Array 2 P-Channel 30V 7A  8-SO")
      (fields (field (name "ALTIUM_UNNAMED_1") "30V 7A"))
      (libsource (lib "TRANSISTORS") (part "FDS4935A"))
    )
    (comp (ref "VT8")
      (value "BSS138")
      (footprint "SOT-23")
      (description "N-Channel 50V 220mA (Ta) 360mW (Ta) Surface Mount SOT-23-3")
      (fields (field (name "PART NUMBER") "BSS138_ON Semiconductor"))
      (libsource (lib "TRANSISTORS") (part "BSS138"))
    )
    (comp (ref "VT9")
      (value "BSS138")
      (footprint "SOT-23")
      (description "N-Channel 50V 220mA (Ta) 360mW (Ta) Surface Mount SOT-23-3")
      (fields (field (name "PART NUMBER") "BSS138_ON Semiconductor"))
      (libsource (lib "TRANSISTORS") (part "BSS138"))
    )
    (comp (ref "VT10")
      (value "FDS4935A")
      (footprint "SO-8_L")
      (description "Mosfet Array 2 P-Channel 30V 7A  8-SO")
      (fields (field (name "ALTIUM_UNNAMED_1") "30V 7A"))
      (libsource (lib "TRANSISTORS") (part "FDS4935A"))
    )
    (comp (ref "VT11")
      (value "BSS138")
      (footprint "SOT-23")
      (description "N-Channel 50V 220mA (Ta) 360mW (Ta) Surface Mount SOT-23-3")
      (fields (field (name "PART NUMBER") "BSS138_ON Semiconductor"))
      (libsource (lib "TRANSISTORS") (part "BSS138"))
    )
    (comp (ref "VT12")
      (value "BSS138")
      (footprint "SOT-23")
      (description "N-Channel 50V 220mA (Ta) 360mW (Ta) Surface Mount SOT-23-3")
      (fields (field (name "PART NUMBER") "BSS138_ON Semiconductor"))
      (libsource (lib "TRANSISTORS") (part "BSS138"))
    )
    (comp (ref "VT13")
      (value "FDS4935A")
      (footprint "SO-8_L")
      (description "Mosfet Array 2 P-Channel 30V 7A  8-SO")
      (fields (field (name "ALTIUM_UNNAMED_1") "30V 7A"))
      (libsource (lib "TRANSISTORS") (part "FDS4935A"))
    )
    (comp (ref "VT14")
      (value "BSS138")
      (footprint "SOT-23")
      (description "N-Channel 50V 220mA (Ta) 360mW (Ta) Surface Mount SOT-23-3")
      (fields (field (name "PART NUMBER") "BSS138_ON Semiconductor"))
      (libsource (lib "TRANSISTORS") (part "BSS138"))
    )
    (comp (ref "VT15")
      (value "BSS138")
      (footprint "SOT-23")
      (description "N-Channel 50V 220mA (Ta) 360mW (Ta) Surface Mount SOT-23-3")
      (fields (field (name "PART NUMBER") "BSS138_ON Semiconductor"))
      (libsource (lib "TRANSISTORS") (part "BSS138"))
    )
    (comp (ref "VT16")
      (value "FDS4935A")
      (footprint "SO-8_L")
      (description "Mosfet Array 2 P-Channel 30V 7A  8-SO")
      (fields (field (name "ALTIUM_UNNAMED_1") "30V 7A"))
      (libsource (lib "TRANSISTORS") (part "FDS4935A"))
    )
    (comp (ref "VT17")
      (value "BSS138")
      (footprint "SOT-23")
      (description "N-Channel 50V 220mA (Ta) 360mW (Ta) Surface Mount SOT-23-3")
      (fields (field (name "PART NUMBER") "BSS138_ON Semiconductor"))
      (libsource (lib "TRANSISTORS") (part "BSS138"))
    )
    (comp (ref "XP1")
      (value "15EDGRC-3.5-02P-14-00AH + 15EDGK-3.5-02P-14-00AH")
      (footprint "15EDGRC-3.5-02P-14-00AH")
      (description "Connector 15EDGRC-3.5-02P-14-00AH + 15EDGK-3.5-02P-14-00AH")
      (libsource (lib "DIGITAL and ANALOG ICs") (part "15EDGRC-3.5-02P-14-00AH"))
    )
    (comp (ref "XP2")
      (value "PLS-4_not_mount")
      (footprint "PLS-4_not_mount")
      (description "Connector PLS-4 (2.54mm x1)")
      (libsource (lib "CONNECTORS") (part "PLS-4_not_mount"))
    )
    (comp (ref "XP3")
      (value "PLS-4_not_mount")
      (footprint "PLS-4_not_mount")
      (description "Connector PLS-4 (2.54mm x1)")
      (libsource (lib "CONNECTORS") (part "PLS-4_not_mount"))
    )
    (comp (ref "XP4")
      (value "15EDGRC-3.5-04P-14-00AH + 15EDGK-3.5-04P-14-00AH")
      (footprint "15EDGRC-3.5-04P-14-00AH")
      (description "Connector 15EDGRC-3.5-04P-14-00AH + 15EDGK-3.5-04P-14-00AH")
      (libsource (lib "CONNECTORS") (part "15EDGRC-3.5-04P-14-00AH"))
    )
    (comp (ref "XP5")
      (value "PLS-4_not_mount")
      (footprint "PLS-4_not_mount")
      (description "Connector PLS-4 (2.54mm x1)")
      (libsource (lib "CONNECTORS") (part "PLS-4_not_mount"))
    )
    (comp (ref "XP6")
      (value "PLS-5_not_mount")
      (footprint "PLS-5_not_mount")
      (description "Connector PLS-5 (2.54mm x1)_not_mount")
      (libsource (lib "CONNECTORS") (part "PLS-5_not_mount"))
    )
    (comp (ref "XP7")
      (value "15EDGRC-3.5-12P-14-00AH")
      (footprint "15EDGRC-3.5-12P-14-00AH")
      (description "15EDGRC-3.5-12P-14-00AH + 15EDGK-3.5-12P-14-00AH")
      (fields (field (name "ALTIUM_UNNAMED_1") "15EDGRC-3.5-12P-14-00AH + 15EDGK-3.5-12P-14-00AH"))
      (libsource (lib "CONNECTORS") (part "15EDGRC-3.5-12P-14-00AH"))
    )
    (comp (ref "XP8")
      (value "USB-micro 5P/F 5-9 SMD-DIP T/R (TYCO 2013499-1)")
      (footprint "TYCO 2013499-1")
      (description "Micro USB 5S-B")
      (libsource (lib "CONNECTORS") (part "USB-micro 5P/F 5-9 SMD-DIP T/R (TYCO 2013499-1)"))
    )
    (comp (ref "XP9")
      (value "15EDGRC-3.5-04P-14-00AH + 15EDGK-3.5-04P-14-00AH")
      (footprint "15EDGRC-3.5-04P-14-00AH")
      (description "Connector 15EDGRC-3.5-04P-14-00AH + 15EDGK-3.5-04P-14-00AH")
      (libsource (lib "CONNECTORS") (part "15EDGRC-3.5-04P-14-00AH"))
    )
    (comp (ref "XS1")
      (value "PBS-4 (DS-1023-1x4)")
      (footprint "PBS-4")
      (description "Connector PBS-04 (2.54mm x1)")
      (libsource (lib "*") (part "PBS-4 (DS-1023-1x4)"))
    )
  )
  (nets
    (net (code "1") (name "/+IN") (class "Default")
      (node (ref "R76") (pin "1") (pintype "passive"))
      (node (ref "VD1") (pin "2") (pinfunction "2_2") (pintype "passive"))
      (node (ref "VD2") (pin "2") (pinfunction "2_2") (pintype "passive"))
      (node (ref "XP1") (pin "1") (pinfunction "1_1") (pintype "passive"))
    )
    (net (code "2") (name "/1_485_A") (class "Default")
      (node (ref "DD2") (pin "6") (pinfunction "A_6") (pintype "passive"))
      (node (ref "R9") (pin "1") (pintype "passive"))
      (node (ref "XP4") (pin "2") (pinfunction "2_2") (pintype "passive"))
    )
    (net (code "3") (name "/1_485_B") (class "Default")
      (node (ref "DD2") (pin "7") (pinfunction "B_7") (pintype "passive"))
      (node (ref "R9") (pin "2") (pintype "passive"))
      (node (ref "XP4") (pin "1") (pinfunction "1_1") (pintype "passive"))
    )
    (net (code "4") (name "/2_485_A") (class "Default")
      (node (ref "DD4") (pin "6") (pinfunction "A_6") (pintype "passive"))
      (node (ref "R23") (pin "2") (pintype "passive"))
      (node (ref "XP4") (pin "4") (pinfunction "4_4") (pintype "passive"))
    )
    (net (code "5") (name "/2_485_B") (class "Default")
      (node (ref "DD4") (pin "7") (pinfunction "B_7") (pintype "passive"))
      (node (ref "R23") (pin "1") (pintype "passive"))
      (node (ref "XP4") (pin "3") (pinfunction "3_3") (pintype "passive"))
    )
    (net (code "6") (name "/BOOT") (class "Default")
      (node (ref "DD1") (pin "44") (pinfunction "BOOT0_44") (pintype "passive"))
      (node (ref "R14") (pin "1") (pintype "passive"))
    )
    (net (code "7") (name "/BUTTON_1") (class "Default")
      (node (ref "DD1") (pin "2") (pinfunction "PC13_2") (pintype "passive"))
      (node (ref "SW1") (pin "1") (pinfunction "1_1") (pintype "passive"))
    )
    (net (code "8") (name "/BUTTON_2") (class "Default")
      (node (ref "DD1") (pin "3") (pinfunction "PC14-OSC32_IN_3") (pintype "passive"))
      (node (ref "SW2") (pin "1") (pinfunction "1_1") (pintype "passive"))
    )
    (net (code "9") (name "/BUTTON_3") (class "Default")
      (node (ref "DD1") (pin "4") (pinfunction "PC15-OSC32_OUT_4") (pintype "passive"))
      (node (ref "SW3") (pin "1") (pinfunction "1_1") (pintype "passive"))
    )
    (net (code "10") (name "/D1") (class "Default")
      (node (ref "DD2") (pin "4") (pinfunction "D_(in)_4") (pintype "passive"))
      (node (ref "PC11") (pin "4") (pintype "passive"))
      (node (ref "PC3") (pin "6") (pintype "passive"))
      (node (ref "R10") (pin "1") (pintype "passive"))
    )
    (net (code "11") (name "/D2") (class "Default")
      (node (ref "DD4") (pin "4") (pinfunction "D_(in)_4") (pintype "passive"))
      (node (ref "PC14") (pin "4") (pintype "passive"))
      (node (ref "PC6") (pin "6") (pintype "passive"))
      (node (ref "R28") (pin "2") (pintype "passive"))
    )
    (net (code "12") (name "/DE1") (class "Default")
      (node (ref "DD2") (pin "2") (pinfunction "RE#_2") (pintype "passive"))
      (node (ref "DD2") (pin "3") (pinfunction "DE_3") (pintype "passive"))
      (node (ref "PC10") (pin "4") (pintype "passive"))
      (node (ref "PC2") (pin "6") (pintype "passive"))
      (node (ref "R6") (pin "1") (pintype "passive"))
    )
    (net (code "13") (name "/DE2") (class "Default")
      (node (ref "DD4") (pin "2") (pinfunction "RE#_2") (pintype "passive"))
      (node (ref "DD4") (pin "3") (pinfunction "DE_3") (pintype "passive"))
      (node (ref "PC13") (pin "4") (pintype "passive"))
      (node (ref "PC5") (pin "6") (pintype "passive"))
      (node (ref "R24") (pin "1") (pintype "passive"))
    )
    (net (code "14") (name "/DEV1") (class "Default")
      (node (ref "PC10") (pin "1") (pintype "passive"))
      (node (ref "PC2") (pin "2") (pintype "passive"))
      (node (ref "R7") (pin "1") (pintype "passive"))
    )
    (net (code "15") (name "/DEV2") (class "Default")
      (node (ref "PC13") (pin "1") (pintype "passive"))
      (node (ref "PC5") (pin "2") (pintype "passive"))
      (node (ref "R25") (pin "1") (pintype "passive"))
    )
    (net (code "16") (name "/DV1") (class "Default")
      (node (ref "PC11") (pin "1") (pintype "passive"))
      (node (ref "PC3") (pin "2") (pintype "passive"))
      (node (ref "R11") (pin "1") (pintype "passive"))
    )
    (net (code "17") (name "/DV2") (class "Default")
      (node (ref "PC14") (pin "1") (pintype "passive"))
      (node (ref "PC6") (pin "2") (pintype "passive"))
      (node (ref "R30") (pin "1") (pintype "passive"))
    )
    (net (code "18") (name "/I2C1_SCL") (class "Default")
      (node (ref "DD1") (pin "42") (pinfunction "PB6/I2C1_SCL_42") (pintype "passive"))
      (node (ref "OLED1") (pin "3") (pinfunction "SCL_3") (pintype "passive"))
      (node (ref "R63") (pin "1") (pintype "passive"))
      (node (ref "XS1") (pin "3") (pinfunction "3_3") (pintype "passive"))
    )
    (net (code "19") (name "/I2C1_SDA") (class "Default")
      (node (ref "DD1") (pin "43") (pinfunction "PB7/I2C1_SDA_43") (pintype "passive"))
      (node (ref "OLED1") (pin "4") (pinfunction "SDA_4") (pintype "passive"))
      (node (ref "R62") (pin "1") (pintype "passive"))
      (node (ref "XS1") (pin "4") (pinfunction "4_4") (pintype "passive"))
    )
    (net (code "20") (name "/LED_1") (class "Default")
      (node (ref "DD1") (pin "39") (pinfunction "PB3_39") (pintype "passive"))
      (node (ref "R38") (pin "2") (pintype "passive"))
    )
    (net (code "21") (name "/LED_2") (class "Default")
      (node (ref "DD1") (pin "40") (pinfunction "PB4_40") (pintype "passive"))
      (node (ref "R44") (pin "2") (pintype "passive"))
    )
    (net (code "22") (name "/LED_3") (class "Default")
      (node (ref "DD1") (pin "41") (pinfunction "PB5_41") (pintype "passive"))
      (node (ref "R46") (pin "2") (pintype "passive"))
    )
    (net (code "23") (name "/NRST") (class "Default")
      (node (ref "C4") (pin "1") (pintype "passive"))
      (node (ref "DD1") (pin "7") (pinfunction "NRST_7") (pintype "passive"))
      (node (ref "XP6") (pin "5") (pinfunction "5_5") (pintype "passive"))
    )
    (net (code "24") (name "/ON_SW_1") (class "Default")
      (node (ref "DD1") (pin "29") (pinfunction "PA8_29") (pintype "passive"))
      (node (ref "R8") (pin "2") (pintype "passive"))
      (node (ref "VT2") (pin "1") (pinfunction "G_1") (pintype "passive"))
    )
    (net (code "25") (name "/ON_SW_2") (class "Default")
      (node (ref "DD1") (pin "28") (pinfunction "PB15_28") (pintype "passive"))
      (node (ref "R16") (pin "2") (pintype "passive"))
      (node (ref "VT3") (pin "1") (pinfunction "G_1") (pintype "passive"))
    )
    (net (code "26") (name "/ON_SW_3") (class "Default")
      (node (ref "DD1") (pin "27") (pinfunction "PB14_27") (pintype "passive"))
      (node (ref "R22") (pin "2") (pintype "passive"))
      (node (ref "VT5") (pin "1") (pinfunction "G_1") (pintype "passive"))
    )
    (net (code "27") (name "/ON_SW_4") (class "Default")
      (node (ref "DD1") (pin "26") (pinfunction "PB13_26") (pintype "passive"))
      (node (ref "R31") (pin "2") (pintype "passive"))
      (node (ref "VT6") (pin "1") (pinfunction "G_1") (pintype "passive"))
    )
    (net (code "28") (name "/ON_SW_5") (class "Default")
      (node (ref "DD1") (pin "25") (pinfunction "PB12_25") (pintype "passive"))
      (node (ref "R35") (pin "2") (pintype "passive"))
      (node (ref "VT8") (pin "1") (pinfunction "G_1") (pintype "passive"))
    )
    (net (code "29") (name "/ON_SW_6") (class "Default")
      (node (ref "DD1") (pin "18") (pinfunction "PB0_18") (pintype "passive"))
      (node (ref "R45") (pin "2") (pintype "passive"))
      (node (ref "VT9") (pin "1") (pinfunction "G_1") (pintype "passive"))
    )
    (net (code "30") (name "/ON_SW_7") (class "Default")
      (node (ref "DD1") (pin "17") (pinfunction "PA7_17") (pintype "passive"))
      (node (ref "R55") (pin "2") (pintype "passive"))
      (node (ref "VT11") (pin "1") (pinfunction "G_1") (pintype "passive"))
    )
    (net (code "31") (name "/ON_SW_8") (class "Default")
      (node (ref "DD1") (pin "16") (pinfunction "PA6_16") (pintype "passive"))
      (node (ref "R60") (pin "2") (pintype "passive"))
      (node (ref "VT12") (pin "1") (pinfunction "G_1") (pintype "passive"))
    )
    (net (code "32") (name "/ON_SW_9") (class "Default")
      (node (ref "DD1") (pin "15") (pinfunction "PA5_15") (pintype "passive"))
      (node (ref "R67") (pin "2") (pintype "passive"))
      (node (ref "VT14") (pin "1") (pinfunction "G_1") (pintype "passive"))
    )
    (net (code "33") (name "/ON_SW_10") (class "Default")
      (node (ref "DD1") (pin "14") (pinfunction "PA4_14") (pintype "passive"))
      (node (ref "R71") (pin "2") (pintype "passive"))
      (node (ref "VT15") (pin "1") (pinfunction "G_1") (pintype "passive"))
    )
    (net (code "34") (name "/ON_SW_11") (class "Default")
      (node (ref "DD1") (pin "10") (pinfunction "PA0_10") (pintype "passive"))
      (node (ref "R75") (pin "2") (pintype "passive"))
      (node (ref "VT17") (pin "1") (pinfunction "G_1") (pintype "passive"))
    )
    (net (code "35") (name "/OUT_SW_1") (class "Default")
      (node (ref "LED1") (pin "2") (pinfunction "A_2") (pintype "passive"))
      (node (ref "VD8") (pin "1") (pinfunction "1_1") (pintype "passive"))
      (node (ref "VT1") (pin "7") (pinfunction "D2_7") (pintype "passive"))
      (node (ref "VT1") (pin "8") (pinfunction "D2_8") (pintype "passive"))
      (node (ref "XP7") (pin "2") (pinfunction "2_2") (pintype "passive"))
    )
    (net (code "36") (name "/OUT_SW_2") (class "Default")
      (node (ref "LED2") (pin "2") (pinfunction "A_2") (pintype "passive"))
      (node (ref "VD9") (pin "1") (pinfunction "1_1") (pintype "passive"))
      (node (ref "VT1") (pin "5") (pinfunction "D1_5") (pintype "passive"))
      (node (ref "VT1") (pin "6") (pinfunction "D1_6") (pintype "passive"))
      (node (ref "XP7") (pin "3") (pinfunction "3_3") (pintype "passive"))
    )
    (net (code "37") (name "/OUT_SW_3") (class "Default")
      (node (ref "LED3") (pin "2") (pinfunction "A_2") (pintype "passive"))
      (node (ref "VD10") (pin "1") (pinfunction "1_1") (pintype "passive"))
      (node (ref "VT4") (pin "7") (pinfunction "D2_7") (pintype "passive"))
      (node (ref "VT4") (pin "8") (pinfunction "D2_8") (pintype "passive"))
      (node (ref "XP7") (pin "4") (pinfunction "4_4") (pintype "passive"))
    )
    (net (code "38") (name "/OUT_SW_4") (class "Default")
      (node (ref "LED4") (pin "2") (pinfunction "A_2") (pintype "passive"))
      (node (ref "VD11") (pin "1") (pinfunction "1_1") (pintype "passive"))
      (node (ref "VT4") (pin "5") (pinfunction "D1_5") (pintype "passive"))
      (node (ref "VT4") (pin "6") (pinfunction "D1_6") (pintype "passive"))
      (node (ref "XP7") (pin "5") (pinfunction "5_5") (pintype "passive"))
    )
    (net (code "39") (name "/OUT_SW_5") (class "Default")
      (node (ref "LED5") (pin "2") (pinfunction "A_2") (pintype "passive"))
      (node (ref "VD12") (pin "1") (pinfunction "1_1") (pintype "passive"))
      (node (ref "VT7") (pin "7") (pinfunction "D2_7") (pintype "passive"))
      (node (ref "VT7") (pin "8") (pinfunction "D2_8") (pintype "passive"))
      (node (ref "XP7") (pin "6") (pinfunction "6_6") (pintype "passive"))
    )
    (net (code "40") (name "/OUT_SW_6") (class "Default")
      (node (ref "LED9") (pin "2") (pinfunction "A_2") (pintype "passive"))
      (node (ref "VD13") (pin "1") (pinfunction "1_1") (pintype "passive"))
      (node (ref "VT7") (pin "5") (pinfunction "D1_5") (pintype "passive"))
      (node (ref "VT7") (pin "6") (pinfunction "D1_6") (pintype "passive"))
      (node (ref "XP7") (pin "7") (pinfunction "7_7") (pintype "passive"))
    )
    (net (code "41") (name "/OUT_SW_7") (class "Default")
      (node (ref "LED12") (pin "2") (pinfunction "A_2") (pintype "passive"))
      (node (ref "VD15") (pin "1") (pinfunction "1_1") (pintype "passive"))
      (node (ref "VT10") (pin "7") (pinfunction "D2_7") (pintype "passive"))
      (node (ref "VT10") (pin "8") (pinfunction "D2_8") (pintype "passive"))
      (node (ref "XP7") (pin "8") (pinfunction "8_8") (pintype "passive"))
    )
    (net (code "42") (name "/OUT_SW_8") (class "Default")
      (node (ref "LED13") (pin "2") (pinfunction "A_2") (pintype "passive"))
      (node (ref "VD17") (pin "1") (pinfunction "1_1") (pintype "passive"))
      (node (ref "VT10") (pin "5") (pinfunction "D1_5") (pintype "passive"))
      (node (ref "VT10") (pin "6") (pinfunction "D1_6") (pintype "passive"))
      (node (ref "XP7") (pin "9") (pinfunction "9_9") (pintype "passive"))
    )
    (net (code "43") (name "/OUT_SW_9") (class "Default")
      (node (ref "LED14") (pin "2") (pinfunction "A_2") (pintype "passive"))
      (node (ref "VD14") (pin "1") (pinfunction "1_1") (pintype "passive"))
      (node (ref "VT13") (pin "7") (pinfunction "D2_7") (pintype "passive"))
      (node (ref "VT13") (pin "8") (pinfunction "D2_8") (pintype "passive"))
      (node (ref "XP7") (pin "10") (pinfunction "10_10") (pintype "passive"))
    )
    (net (code "44") (name "/OUT_SW_10") (class "Default")
      (node (ref "LED15") (pin "2") (pinfunction "A_2") (pintype "passive"))
      (node (ref "VD16") (pin "1") (pinfunction "1_1") (pintype "passive"))
      (node (ref "VT13") (pin "5") (pinfunction "D1_5") (pintype "passive"))
      (node (ref "VT13") (pin "6") (pinfunction "D1_6") (pintype "passive"))
      (node (ref "XP7") (pin "11") (pinfunction "11_11") (pintype "passive"))
    )
    (net (code "45") (name "/OUT_SW_11") (class "Default")
      (node (ref "LED16") (pin "2") (pinfunction "A_2") (pintype "passive"))
      (node (ref "VD18") (pin "1") (pinfunction "1_1") (pintype "passive"))
      (node (ref "VT16") (pin "7") (pinfunction "D2_7") (pintype "passive"))
      (node (ref "VT16") (pin "8") (pinfunction "D2_8") (pintype "passive"))
      (node (ref "XP7") (pin "12") (pinfunction "12_12") (pintype "passive"))
    )
    (net (code "46") (name "/R1") (class "Default")
      (node (ref "PC1") (pin "3") (pintype "passive"))
      (node (ref "PC9") (pin "2") (pintype "passive"))
      (node (ref "R5") (pin "1") (pintype "passive"))
    )
    (net (code "47") (name "/R2") (class "Default")
      (node (ref "PC12") (pin "2") (pintype "passive"))
      (node (ref "PC4") (pin "3") (pintype "passive"))
      (node (ref "R21") (pin "1") (pintype "passive"))
    )
    (net (code "48") (name "/RX") (class "Default")
      (node (ref "DD5") (pin "25") (pinfunction "RXD_25") (pintype "input"))
      (node (ref "PC8") (pin "4") (pintype "passive"))
      (node (ref "R37") (pin "2") (pintype "passive"))
      (node (ref "R47") (pin "1") (pintype "passive"))
      (node (ref "R53") (pin "1") (pintype "passive"))
      (node (ref "R59") (pin "1") (pintype "passive"))
      (node (ref "VD6") (pin "2") (pinfunction "2_2") (pintype "passive"))
    )
    (net (code "49") (name "/RX_T") (class "Default")
      (node (ref "R59") (pin "2") (pintype "passive"))
      (node (ref "XP9") (pin "3") (pinfunction "3_3") (pintype "passive"))
    )
    (net (code "50") (name "/SWCLK") (class "Default")
      (node (ref "DD1") (pin "37") (pinfunction "PA14_37") (pintype "passive"))
      (node (ref "XP6") (pin "2") (pinfunction "2_2") (pintype "passive"))
    )
    (net (code "51") (name "/SWDIO") (class "Default")
      (node (ref "DD1") (pin "34") (pinfunction "PA13_34") (pintype "passive"))
      (node (ref "XP6") (pin "4") (pinfunction "4_4") (pintype "passive"))
    )
    (net (code "52") (name "/TX") (class "Default")
      (node (ref "PC7") (pin "2") (pintype "passive"))
      (node (ref "R36") (pin "2") (pintype "passive"))
      (node (ref "R51") (pin "1") (pintype "passive"))
      (node (ref "R61") (pin "1") (pintype "passive"))
      (node (ref "VD3") (pin "2") (pinfunction "2_2") (pintype "passive"))
      (node (ref "VD7") (pin "2") (pinfunction "2_2") (pintype "passive"))
    )
    (net (code "53") (name "/TX_T") (class "Default")
      (node (ref "R61") (pin "2") (pintype "passive"))
      (node (ref "XP9") (pin "4") (pinfunction "4_4") (pintype "passive"))
    )
    (net (code "54") (name "/USART1_DE") (class "Default")
      (node (ref "DD1") (pin "33") (pinfunction "PA12/USART1_DE_33") (pintype "passive"))
      (node (ref "XP2") (pin "3") (pinfunction "3_3") (pintype "passive"))
    )
    (net (code "55") (name "/USART1_RX") (class "Default")
      (node (ref "DD1") (pin "31") (pinfunction "PA10/USART1_RX_31") (pintype "passive"))
      (node (ref "PC7") (pin "4") (pintype "passive"))
      (node (ref "R40") (pin "1") (pintype "passive"))
      (node (ref "R51") (pin "2") (pintype "passive"))
      (node (ref "XP2") (pin "1") (pinfunction "1_1") (pintype "passive"))
    )
    (net (code "56") (name "/USART1_TX") (class "Default")
      (node (ref "DD1") (pin "30") (pinfunction "PA9/USART1_TX_30") (pintype "passive"))
      (node (ref "PC8") (pin "2") (pintype "passive"))
      (node (ref "R53") (pin "2") (pintype "passive"))
      (node (ref "XP2") (pin "2") (pinfunction "2_2") (pintype "passive"))
    )
    (net (code "57") (name "/USART2_DE") (class "Default")
      (node (ref "DD1") (pin "11") (pinfunction "PA1/USART2_DE_11") (pintype "passive"))
      (node (ref "PC10") (pin "2") (pintype "passive"))
      (node (ref "PC2") (pin "3") (pintype "passive"))
      (node (ref "XP3") (pin "3") (pinfunction "3_3") (pintype "passive"))
    )
    (net (code "58") (name "/USART2_RX") (class "Default")
      (node (ref "DD1") (pin "13") (pinfunction "PA3/USART2_RX_13") (pintype "passive"))
      (node (ref "PC1") (pin "6") (pintype "passive"))
      (node (ref "PC9") (pin "4") (pintype "passive"))
      (node (ref "R1") (pin "1") (pintype "passive"))
      (node (ref "XP3") (pin "1") (pinfunction "1_1") (pintype "passive"))
    )
    (net (code "59") (name "/USART2_TX") (class "Default")
      (node (ref "DD1") (pin "12") (pinfunction "PA2/USART2_TX_12") (pintype "passive"))
      (node (ref "PC11") (pin "2") (pintype "passive"))
      (node (ref "PC3") (pin "3") (pintype "passive"))
      (node (ref "XP3") (pin "2") (pinfunction "2_2") (pintype "passive"))
    )
    (net (code "60") (name "/USART3_DE") (class "Default")
      (node (ref "DD1") (pin "19") (pinfunction "PB1/USART3_DE_19") (pintype "passive"))
      (node (ref "PC13") (pin "2") (pintype "passive"))
      (node (ref "PC5") (pin "3") (pintype "passive"))
      (node (ref "XP5") (pin "3") (pinfunction "3_3") (pintype "passive"))
    )
    (net (code "61") (name "/USART3_RX") (class "Default")
      (node (ref "DD1") (pin "22") (pinfunction "PB11/USART3_RX_22") (pintype "passive"))
      (node (ref "PC12") (pin "4") (pintype "passive"))
      (node (ref "PC4") (pin "6") (pintype "passive"))
      (node (ref "R20") (pin "1") (pintype "passive"))
      (node (ref "XP5") (pin "1") (pinfunction "1_1") (pintype "passive"))
    )
    (net (code "62") (name "/USART3_TX") (class "Default")
      (node (ref "DD1") (pin "21") (pinfunction "PB10/USART3_TX_21") (pintype "passive"))
      (node (ref "PC14") (pin "2") (pintype "passive"))
      (node (ref "PC6") (pin "3") (pintype "passive"))
      (node (ref "XP5") (pin "2") (pinfunction "2_2") (pintype "passive"))
    )
    (net (code "63") (name "/USB_D_N") (class "Default")
      (node (ref "DD5") (pin "5") (pinfunction "D-_5") (pintype "passive"))
      (node (ref "VD5") (pin "2") (pinfunction "2_2") (pintype "passive"))
      (node (ref "XP8") (pin "D-") (pinfunction "D-_D-") (pintype "passive"))
    )
    (net (code "64") (name "/USB_D_P") (class "Default")
      (node (ref "DD5") (pin "4") (pinfunction "D+_4") (pintype "passive"))
      (node (ref "VD4") (pin "2") (pinfunction "2_2") (pintype "passive"))
      (node (ref "XP8") (pin "D+") (pinfunction "D+_D+") (pintype "passive"))
    )
    (net (code "65") (name "3V3") (class "Default")
      (node (ref "C11") (pin "2") (pintype "passive"))
      (node (ref "C12") (pin "2") (pintype "passive"))
      (node (ref "C19") (pin "1") (pintype "passive"))
      (node (ref "C5") (pin "2") (pintype "passive"))
      (node (ref "C6") (pin "2") (pintype "passive"))
      (node (ref "C7") (pin "2") (pintype "passive"))
      (node (ref "C8") (pin "2") (pintype "passive"))
      (node (ref "C9") (pin "2") (pintype "passive"))
      (node (ref "DD1") (pin "1") (pinfunction "VDD_1") (pintype "passive"))
      (node (ref "DD1") (pin "24") (pinfunction "VDD_24") (pintype "passive"))
      (node (ref "DD1") (pin "36") (pinfunction "VDD_36") (pintype "passive"))
      (node (ref "DD1") (pin "48") (pinfunction "VDD_48") (pintype "passive"))
      (node (ref "DD1") (pin "9") (pinfunction "VDDA_9") (pintype "passive"))
      (node (ref "DD3") (pin "2") (pinfunction "V_OUT_2") (pintype "passive"))
      (node (ref "DD3") (pin "4") (pinfunction "V_OUT_4") (pintype "passive"))
      (node (ref "OLED1") (pin "2") (pinfunction "VCC_2") (pintype "passive"))
      (node (ref "R1") (pin "2") (pintype "passive"))
      (node (ref "R11") (pin "2") (pintype "passive"))
      (node (ref "R20") (pin "2") (pintype "passive"))
      (node (ref "R25") (pin "2") (pintype "passive"))
      (node (ref "R30") (pin "2") (pintype "passive"))
      (node (ref "R40") (pin "2") (pintype "passive"))
      (node (ref "R48") (pin "2") (pintype "passive"))
      (node (ref "R62") (pin "2") (pintype "passive"))
      (node (ref "R63") (pin "2") (pintype "passive"))
      (node (ref "R7") (pin "2") (pintype "passive"))
      (node (ref "R77") (pin "2") (pintype "passive"))
      (node (ref "XP6") (pin "1") (pinfunction "1_1") (pintype "passive"))
      (node (ref "XS1") (pin "2") (pinfunction "2_2") (pintype "passive"))
    )
    (net (code "66") (name "3VCP") (class "Default")
      (node (ref "C24") (pin "1") (pintype "passive"))
      (node (ref "DD5") (pin "6") (pinfunction "VDD_6") (pintype "passive"))
      (node (ref "LED7") (pin "2") (pinfunction "A_2") (pintype "passive"))
      (node (ref "LED8") (pin "2") (pinfunction "A_2") (pintype "passive"))
      (node (ref "R39") (pin "2") (pintype "passive"))
      (node (ref "R47") (pin "2") (pintype "passive"))
      (node (ref "R77") (pin "1") (pintype "passive"))
      (node (ref "XP9") (pin "1") (pinfunction "1_1") (pintype "passive"))
    )
    (net (code "67") (name "5V") (class "Default")
      (node (ref "C15") (pin "2") (pintype "passive"))
      (node (ref "C16") (pin "2") (pintype "passive"))
      (node (ref "C21") (pin "2") (pintype "passive"))
      (node (ref "C28") (pin "2") (pintype "passive"))
      (node (ref "DA1") (pin "2") (pinfunction "V_OUT_2") (pintype "passive"))
      (node (ref "DA1") (pin "4") (pinfunction "V_OUT_4") (pintype "passive"))
      (node (ref "L1") (pin "1") (pintype "passive"))
      (node (ref "L2") (pin "1") (pintype "passive"))
      (node (ref "PC1") (pin "7") (pinfunction "EN_7") (pintype "passive"))
      (node (ref "PC1") (pin "8") (pinfunction "VCC_8") (pintype "passive"))
      (node (ref "PC4") (pin "7") (pinfunction "EN_7") (pintype "passive"))
      (node (ref "PC4") (pin "8") (pinfunction "VCC_8") (pintype "passive"))
    )
    (net (code "68") (name "5V_A") (class "Default")
      (node (ref "C1") (pin "1") (pintype "passive"))
      (node (ref "C18") (pin "2") (pintype "passive"))
      (node (ref "DD2") (pin "8") (pinfunction "VCC_8") (pintype "passive"))
      (node (ref "PC1") (pin "2") (pintype "passive"))
      (node (ref "PC2") (pin "7") (pinfunction "EN_7") (pintype "passive"))
      (node (ref "PC2") (pin "8") (pinfunction "VCC_8") (pintype "passive"))
      (node (ref "PC3") (pin "7") (pinfunction "EN_7") (pintype "passive"))
      (node (ref "PC3") (pin "8") (pinfunction "VCC_8") (pintype "passive"))
      (node (ref "PC9") (pin "1") (pintype "passive"))
      (node (ref "R10") (pin "2") (pintype "passive"))
      (node (ref "R6") (pin "2") (pintype "passive"))
      (node (ref "TR1") (pin "4") (pinfunction "+Vout_4") (pintype "passive"))
    )
    (net (code "69") (name "5V_B") (class "Default")
      (node (ref "C13") (pin "1") (pintype "passive"))
      (node (ref "C22") (pin "2") (pintype "passive"))
      (node (ref "DD4") (pin "8") (pinfunction "VCC_8") (pintype "passive"))
      (node (ref "PC12") (pin "1") (pintype "passive"))
      (node (ref "PC4") (pin "2") (pintype "passive"))
      (node (ref "PC5") (pin "7") (pinfunction "EN_7") (pintype "passive"))
      (node (ref "PC5") (pin "8") (pinfunction "VCC_8") (pintype "passive"))
      (node (ref "PC6") (pin "7") (pinfunction "EN_7") (pintype "passive"))
      (node (ref "PC6") (pin "8") (pinfunction "VCC_8") (pintype "passive"))
      (node (ref "R24") (pin "2") (pintype "passive"))
      (node (ref "R28") (pin "1") (pintype "passive"))
      (node (ref "TR2") (pin "4") (pinfunction "+Vout_4") (pintype "passive"))
    )
    (net (code "70") (name "5V_USB") (class "Default")
      (node (ref "C23") (pin "1") (pintype "passive"))
      (node (ref "DD5") (pin "7") (pinfunction "REGIN_7") (pintype "input"))
      (node (ref "DD5") (pin "8") (pinfunction "VBUS_8") (pintype "output"))
      (node (ref "XP8") (pin "VBUS") (pinfunction "VBUS_VBUS") (pintype "passive"))
    )
    (net (code "71") (name "12V") (class "Default")
      (node (ref "C10") (pin "2") (pintype "passive"))
      (node (ref "C14") (pin "2") (pintype "passive"))
      (node (ref "C2") (pin "2") (pintype "passive"))
      (node (ref "C3") (pin "2") (pintype "passive"))
      (node (ref "DA1") (pin "3") (pinfunction "V_IN_3") (pintype "passive"))
      (node (ref "DD3") (pin "3") (pinfunction "V_IN_3") (pintype "passive"))
      (node (ref "R12") (pin "2") (pintype "passive"))
      (node (ref "R17") (pin "2") (pintype "passive"))
      (node (ref "R26") (pin "2") (pintype "passive"))
      (node (ref "R32") (pin "2") (pintype "passive"))
      (node (ref "R4") (pin "2") (pintype "passive"))
      (node (ref "R41") (pin "2") (pintype "passive"))
      (node (ref "R49") (pin "2") (pintype "passive"))
      (node (ref "R56") (pin "2") (pintype "passive"))
      (node (ref "R64") (pin "2") (pintype "passive"))
      (node (ref "R68") (pin "2") (pintype "passive"))
      (node (ref "R72") (pin "2") (pintype "passive"))
      (node (ref "R76") (pin "2") (pintype "passive"))
      (node (ref "VD1") (pin "1") (pinfunction "1_1") (pintype "passive"))
      (node (ref "VD19") (pin "1") (pinfunction "1_1") (pintype "passive"))
      (node (ref "VD2") (pin "1") (pinfunction "1_1") (pintype "passive"))
      (node (ref "VT1") (pin "1") (pinfunction "S2_1") (pintype "passive"))
      (node (ref "VT1") (pin "3") (pinfunction "S1_3") (pintype "passive"))
      (node (ref "VT10") (pin "1") (pinfunction "S2_1") (pintype "passive"))
      (node (ref "VT10") (pin "3") (pinfunction "S1_3") (pintype "passive"))
      (node (ref "VT13") (pin "1") (pinfunction "S2_1") (pintype "passive"))
      (node (ref "VT13") (pin "3") (pinfunction "S1_3") (pintype "passive"))
      (node (ref "VT16") (pin "1") (pinfunction "S2_1") (pintype "passive"))
      (node (ref "VT4") (pin "1") (pinfunction "S2_1") (pintype "passive"))
      (node (ref "VT4") (pin "3") (pinfunction "S1_3") (pintype "passive"))
      (node (ref "VT7") (pin "1") (pinfunction "S2_1") (pintype "passive"))
      (node (ref "VT7") (pin "3") (pinfunction "S1_3") (pintype "passive"))
    )
    (net (code "72") (name "AGND") (class "Default")
      (node (ref "C1") (pin "2") (pintype "passive"))
      (node (ref "C18") (pin "1") (pintype "passive"))
      (node (ref "DD2") (pin "5") (pinfunction "GND_5") (pintype "passive"))
      (node (ref "PC10") (pin "3") (pintype "passive"))
      (node (ref "PC11") (pin "3") (pintype "passive"))
      (node (ref "PC2") (pin "5") (pintype "passive"))
      (node (ref "PC3") (pin "5") (pintype "passive"))
      (node (ref "TR1") (pin "3") (pinfunction "-Vout_3") (pintype "passive"))
    )
    (net (code "73") (name "BGND") (class "Default")
      (node (ref "C13") (pin "2") (pintype "passive"))
      (node (ref "C22") (pin "1") (pintype "passive"))
      (node (ref "DD4") (pin "5") (pinfunction "GND_5") (pintype "passive"))
      (node (ref "PC13") (pin "3") (pintype "passive"))
      (node (ref "PC14") (pin "3") (pintype "passive"))
      (node (ref "PC5") (pin "5") (pintype "passive"))
      (node (ref "PC6") (pin "5") (pintype "passive"))
      (node (ref "TR2") (pin "3") (pinfunction "-Vout_3") (pintype "passive"))
    )
    (net (code "74") (name "GND") (class "Default")
      (node (ref "C10") (pin "1") (pintype "passive"))
      (node (ref "C11") (pin "1") (pintype "passive"))
      (node (ref "C12") (pin "1") (pintype "passive"))
      (node (ref "C14") (pin "1") (pintype "passive"))
      (node (ref "C15") (pin "1") (pintype "passive"))
      (node (ref "C16") (pin "1") (pintype "passive"))
      (node (ref "C17") (pin "2") (pintype "passive"))
      (node (ref "C19") (pin "2") (pintype "passive"))
      (node (ref "C2") (pin "1") (pintype "passive"))
      (node (ref "C20") (pin "1") (pintype "passive"))
      (node (ref "C21") (pin "1") (pintype "passive"))
      (node (ref "C28") (pin "1") (pintype "passive"))
      (node (ref "C3") (pin "1") (pintype "passive"))
      (node (ref "C4") (pin "2") (pintype "passive"))
      (node (ref "C5") (pin "1") (pintype "passive"))
      (node (ref "C6") (pin "1") (pintype "passive"))
      (node (ref "C7") (pin "1") (pintype "passive"))
      (node (ref "C8") (pin "1") (pintype "passive"))
      (node (ref "C9") (pin "1") (pintype "passive"))
      (node (ref "DA1") (pin "1") (pinfunction "GND_1") (pintype "passive"))
      (node (ref "DD1") (pin "23") (pinfunction "VSS_23") (pintype "passive"))
      (node (ref "DD1") (pin "35") (pinfunction "VSS_35") (pintype "passive"))
      (node (ref "DD1") (pin "47") (pinfunction "VSS_47") (pintype "passive"))
      (node (ref "DD1") (pin "8") (pinfunction "VSSA_8") (pintype "passive"))
      (node (ref "DD3") (pin "1") (pinfunction "GND_1") (pintype "passive"))
      (node (ref "LED10") (pin "1") (pinfunction "K_1") (pintype "passive"))
      (node (ref "LED11") (pin "1") (pinfunction "K_1") (pintype "passive"))
      (node (ref "LED6") (pin "1") (pinfunction "K_1") (pintype "passive"))
      (node (ref "OLED1") (pin "1") (pinfunction "GND_1") (pintype "passive"))
      (node (ref "PC1") (pin "5") (pintype "passive"))
      (node (ref "PC12") (pin "3") (pintype "passive"))
      (node (ref "PC4") (pin "5") (pintype "passive"))
      (node (ref "PC7") (pin "3") (pintype "passive"))
      (node (ref "PC9") (pin "3") (pintype "passive"))
      (node (ref "R13") (pin "1") (pintype "passive"))
      (node (ref "R14") (pin "2") (pintype "passive"))
      (node (ref "R16") (pin "1") (pintype "passive"))
      (node (ref "R18") (pin "1") (pintype "passive"))
      (node (ref "R22") (pin "1") (pintype "passive"))
      (node (ref "R27") (pin "1") (pintype "passive"))
      (node (ref "R3") (pin "1") (pintype "passive"))
      (node (ref "R31") (pin "1") (pintype "passive"))
      (node (ref "R33") (pin "1") (pintype "passive"))
      (node (ref "R35") (pin "1") (pintype "passive"))
      (node (ref "R42") (pin "1") (pintype "passive"))
      (node (ref "R45") (pin "1") (pintype "passive"))
      (node (ref "R50") (pin "1") (pintype "passive"))
      (node (ref "R54") (pin "2") (pintype "passive"))
      (node (ref "R55") (pin "1") (pintype "passive"))
      (node (ref "R57") (pin "1") (pintype "passive"))
      (node (ref "R60") (pin "1") (pintype "passive"))
      (node (ref "R66") (pin "1") (pintype "passive"))
      (node (ref "R67") (pin "1") (pintype "passive"))
      (node (ref "R70") (pin "1") (pintype "passive"))
      (node (ref "R71") (pin "1") (pintype "passive"))
      (node (ref "R74") (pin "1") (pintype "passive"))
      (node (ref "R75") (pin "1") (pintype "passive"))
      (node (ref "R8") (pin "1") (pintype "passive"))
      (node (ref "SW1") (pin "2") (pinfunction "2_2") (pintype "passive"))
      (node (ref "SW2") (pin "2") (pinfunction "2_2") (pintype "passive"))
      (node (ref "SW3") (pin "2") (pinfunction "2_2") (pintype "passive"))
      (node (ref "TR1") (pin "1") (pinfunction "-Vin_1") (pintype "passive"))
      (node (ref "TR2") (pin "1") (pinfunction "-Vin_1") (pintype "passive"))
      (node (ref "VD10") (pin "2") (pinfunction "2_2") (pintype "passive"))
      (node (ref "VD11") (pin "2") (pinfunction "2_2") (pintype "passive"))
      (node (ref "VD12") (pin "2") (pinfunction "2_2") (pintype "passive"))
      (node (ref "VD13") (pin "2") (pinfunction "2_2") (pintype "passive"))
      (node (ref "VD14") (pin "2") (pinfunction "2_2") (pintype "passive"))
      (node (ref "VD15") (pin "2") (pinfunction "2_2") (pintype "passive"))
      (node (ref "VD16") (pin "2") (pinfunction "2_2") (pintype "passive"))
      (node (ref "VD17") (pin "2") (pinfunction "2_2") (pintype "passive"))
      (node (ref "VD18") (pin "2") (pinfunction "2_2") (pintype "passive"))
      (node (ref "VD19") (pin "2") (pinfunction "2_2") (pintype "passive"))
      (node (ref "VD8") (pin "2") (pinfunction "2_2") (pintype "passive"))
      (node (ref "VD9") (pin "2") (pinfunction "2_2") (pintype "passive"))
      (node (ref "VT11") (pin "2") (pinfunction "S_2") (pintype "passive"))
      (node (ref "VT12") (pin "2") (pinfunction "S_2") (pintype "passive"))
      (node (ref "VT14") (pin "2") (pinfunction "S_2") (pintype "passive"))
      (node (ref "VT15") (pin "2") (pinfunction "S_2") (pintype "passive"))
      (node (ref "VT17") (pin "2") (pinfunction "S_2") (pintype "passive"))
      (node (ref "VT2") (pin "2") (pinfunction "S_2") (pintype "passive"))
      (node (ref "VT3") (pin "2") (pinfunction "S_2") (pintype "passive"))
      (node (ref "VT5") (pin "2") (pinfunction "S_2") (pintype "passive"))
      (node (ref "VT6") (pin "2") (pinfunction "S_2") (pintype "passive"))
      (node (ref "VT8") (pin "2") (pinfunction "S_2") (pintype "passive"))
      (node (ref "VT9") (pin "2") (pinfunction "S_2") (pintype "passive"))
      (node (ref "XP1") (pin "2") (pinfunction "2_2") (pintype "passive"))
      (node (ref "XP2") (pin "4") (pinfunction "4_4") (pintype "passive"))
      (node (ref "XP3") (pin "4") (pinfunction "4_4") (pintype "passive"))
      (node (ref "XP5") (pin "4") (pinfunction "4_4") (pintype "passive"))
      (node (ref "XP6") (pin "3") (pinfunction "3_3") (pintype "passive"))
      (node (ref "XP7") (pin "1") (pinfunction "1_1") (pintype "passive"))
      (node (ref "XS1") (pin "1") (pinfunction "1_1") (pintype "passive"))
    )
    (net (code "75") (name "Net-(DD2-R_(out))") (class "Default")
      (node (ref "DD2") (pin "1") (pinfunction "R_(out)_1") (pintype "passive"))
      (node (ref "R5") (pin "2") (pintype "passive"))
    )
    (net (code "76") (name "Net-(DD4-R_(out))") (class "Default")
      (node (ref "DD4") (pin "1") (pinfunction "R_(out)_1") (pintype "passive"))
      (node (ref "R21") (pin "2") (pintype "passive"))
    )
    (net (code "77") (name "Net-(DD5-TXD)") (class "Default")
      (node (ref "DD5") (pin "26") (pinfunction "TXD_26") (pintype "output"))
      (node (ref "VD3") (pin "1") (pinfunction "1_1") (pintype "passive"))
    )
    (net (code "78") (name "Net-(LED1-K)") (class "Default")
      (node (ref "LED1") (pin "1") (pinfunction "K_1") (pintype "passive"))
      (node (ref "R3") (pin "2") (pintype "passive"))
    )
    (net (code "79") (name "Net-(LED2-K)") (class "Default")
      (node (ref "LED2") (pin "1") (pinfunction "K_1") (pintype "passive"))
      (node (ref "R13") (pin "2") (pintype "passive"))
    )
    (net (code "80") (name "Net-(LED3-K)") (class "Default")
      (node (ref "LED3") (pin "1") (pinfunction "K_1") (pintype "passive"))
      (node (ref "R18") (pin "2") (pintype "passive"))
    )
    (net (code "81") (name "Net-(LED4-K)") (class "Default")
      (node (ref "LED4") (pin "1") (pinfunction "K_1") (pintype "passive"))
      (node (ref "R27") (pin "2") (pintype "passive"))
    )
    (net (code "82") (name "Net-(LED5-K)") (class "Default")
      (node (ref "LED5") (pin "1") (pinfunction "K_1") (pintype "passive"))
      (node (ref "R33") (pin "2") (pintype "passive"))
    )
    (net (code "83") (name "Net-(LED6-A)") (class "Default")
      (node (ref "LED6") (pin "2") (pinfunction "A_2") (pintype "passive"))
      (node (ref "R38") (pin "1") (pintype "passive"))
    )
    (net (code "84") (name "Net-(LED7-K)") (class "Default")
      (node (ref "LED7") (pin "1") (pinfunction "K_1") (pintype "passive"))
      (node (ref "R37") (pin "1") (pintype "passive"))
    )
    (net (code "85") (name "Net-(LED8-K)") (class "Default")
      (node (ref "LED8") (pin "1") (pinfunction "K_1") (pintype "passive"))
      (node (ref "R36") (pin "1") (pintype "passive"))
    )
    (net (code "86") (name "Net-(LED9-K)") (class "Default")
      (node (ref "LED9") (pin "1") (pinfunction "K_1") (pintype "passive"))
      (node (ref "R42") (pin "2") (pintype "passive"))
    )
    (net (code "87") (name "Net-(LED10-A)") (class "Default")
      (node (ref "LED10") (pin "2") (pinfunction "A_2") (pintype "passive"))
      (node (ref "R44") (pin "1") (pintype "passive"))
    )
    (net (code "88") (name "Net-(LED11-A)") (class "Default")
      (node (ref "LED11") (pin "2") (pinfunction "A_2") (pintype "passive"))
      (node (ref "R46") (pin "1") (pintype "passive"))
    )
    (net (code "89") (name "Net-(LED12-K)") (class "Default")
      (node (ref "LED12") (pin "1") (pinfunction "K_1") (pintype "passive"))
      (node (ref "R50") (pin "2") (pintype "passive"))
    )
    (net (code "90") (name "Net-(LED13-K)") (class "Default")
      (node (ref "LED13") (pin "1") (pinfunction "K_1") (pintype "passive"))
      (node (ref "R57") (pin "2") (pintype "passive"))
    )
    (net (code "91") (name "Net-(LED14-K)") (class "Default")
      (node (ref "LED14") (pin "1") (pinfunction "K_1") (pintype "passive"))
      (node (ref "R66") (pin "2") (pintype "passive"))
    )
    (net (code "92") (name "Net-(LED15-K)") (class "Default")
      (node (ref "LED15") (pin "1") (pinfunction "K_1") (pintype "passive"))
      (node (ref "R70") (pin "2") (pintype "passive"))
    )
    (net (code "93") (name "Net-(LED16-K)") (class "Default")
      (node (ref "LED16") (pin "1") (pinfunction "K_1") (pintype "passive"))
      (node (ref "R74") (pin "2") (pintype "passive"))
    )
    (net (code "94") (name "Net-(PC7-Pad1)") (class "Default")
      (node (ref "PC7") (pin "1") (pintype "passive"))
      (node (ref "R39") (pin "1") (pintype "passive"))
    )
    (net (code "95") (name "Net-(PC8-Pad1)") (class "Default")
      (node (ref "PC8") (pin "1") (pintype "passive"))
      (node (ref "R48") (pin "1") (pintype "passive"))
    )
    (net (code "96") (name "Net-(TR1-+Vin)") (class "Default")
      (node (ref "C17") (pin "1") (pintype "passive"))
      (node (ref "L1") (pin "2") (pintype "passive"))
      (node (ref "TR1") (pin "2") (pinfunction "+Vin_2") (pintype "power_in"))
    )
    (net (code "97") (name "Net-(TR2-+Vin)") (class "Default")
      (node (ref "C20") (pin "2") (pintype "passive"))
      (node (ref "L2") (pin "2") (pintype "passive"))
      (node (ref "TR2") (pin "2") (pinfunction "+Vin_2") (pintype "power_in"))
    )
    (net (code "98") (name "Net-(VT1A-G1)") (class "Default")
      (node (ref "R12") (pin "1") (pintype "passive"))
      (node (ref "R15") (pin "1") (pintype "passive"))
      (node (ref "VT1") (pin "4") (pinfunction "G1_4") (pintype "passive"))
    )
    (net (code "99") (name "Net-(VT1B-G2)") (class "Default")
      (node (ref "R2") (pin "1") (pintype "passive"))
      (node (ref "R4") (pin "1") (pintype "passive"))
      (node (ref "VT1") (pin "2") (pinfunction "G2_2") (pintype "passive"))
    )
    (net (code "100") (name "Net-(VT2-D)") (class "Default")
      (node (ref "R2") (pin "2") (pintype "passive"))
      (node (ref "VT2") (pin "3") (pinfunction "D_3") (pintype "passive"))
    )
    (net (code "101") (name "Net-(VT3-D)") (class "Default")
      (node (ref "R15") (pin "2") (pintype "passive"))
      (node (ref "VT3") (pin "3") (pinfunction "D_3") (pintype "passive"))
    )
    (net (code "102") (name "Net-(VT4A-G1)") (class "Default")
      (node (ref "R26") (pin "1") (pintype "passive"))
      (node (ref "R29") (pin "1") (pintype "passive"))
      (node (ref "VT4") (pin "4") (pinfunction "G1_4") (pintype "passive"))
    )
    (net (code "103") (name "Net-(VT4B-G2)") (class "Default")
      (node (ref "R17") (pin "1") (pintype "passive"))
      (node (ref "R19") (pin "1") (pintype "passive"))
      (node (ref "VT4") (pin "2") (pinfunction "G2_2") (pintype "passive"))
    )
    (net (code "104") (name "Net-(VT5-D)") (class "Default")
      (node (ref "R19") (pin "2") (pintype "passive"))
      (node (ref "VT5") (pin "3") (pinfunction "D_3") (pintype "passive"))
    )
    (net (code "105") (name "Net-(VT6-D)") (class "Default")
      (node (ref "R29") (pin "2") (pintype "passive"))
      (node (ref "VT6") (pin "3") (pinfunction "D_3") (pintype "passive"))
    )
    (net (code "106") (name "Net-(VT7A-G1)") (class "Default")
      (node (ref "R41") (pin "1") (pintype "passive"))
      (node (ref "R43") (pin "1") (pintype "passive"))
      (node (ref "VT7") (pin "4") (pinfunction "G1_4") (pintype "passive"))
    )
    (net (code "107") (name "Net-(VT7B-G2)") (class "Default")
      (node (ref "R32") (pin "1") (pintype "passive"))
      (node (ref "R34") (pin "1") (pintype "passive"))
      (node (ref "VT7") (pin "2") (pinfunction "G2_2") (pintype "passive"))
    )
    (net (code "108") (name "Net-(VT8-D)") (class "Default")
      (node (ref "R34") (pin "2") (pintype "passive"))
      (node (ref "VT8") (pin "3") (pinfunction "D_3") (pintype "passive"))
    )
    (net (code "109") (name "Net-(VT9-D)") (class "Default")
      (node (ref "R43") (pin "2") (pintype "passive"))
      (node (ref "VT9") (pin "3") (pinfunction "D_3") (pintype "passive"))
    )
    (net (code "110") (name "Net-(VT10A-G1)") (class "Default")
      (node (ref "R56") (pin "1") (pintype "passive"))
      (node (ref "R58") (pin "1") (pintype "passive"))
      (node (ref "VT10") (pin "4") (pinfunction "G1_4") (pintype "passive"))
    )
    (net (code "111") (name "Net-(VT10B-G2)") (class "Default")
      (node (ref "R49") (pin "1") (pintype "passive"))
      (node (ref "R52") (pin "1") (pintype "passive"))
      (node (ref "VT10") (pin "2") (pinfunction "G2_2") (pintype "passive"))
    )
    (net (code "112") (name "Net-(VT11-D)") (class "Default")
      (node (ref "R52") (pin "2") (pintype "passive"))
      (node (ref "VT11") (pin "3") (pinfunction "D_3") (pintype "passive"))
    )
    (net (code "113") (name "Net-(VT12-D)") (class "Default")
      (node (ref "R58") (pin "2") (pintype "passive"))
      (node (ref "VT12") (pin "3") (pinfunction "D_3") (pintype "passive"))
    )
    (net (code "114") (name "Net-(VT13A-G1)") (class "Default")
      (node (ref "R68") (pin "1") (pintype "passive"))
      (node (ref "R69") (pin "1") (pintype "passive"))
      (node (ref "VT13") (pin "4") (pinfunction "G1_4") (pintype "passive"))
    )
    (net (code "115") (name "Net-(VT13B-G2)") (class "Default")
      (node (ref "R64") (pin "1") (pintype "passive"))
      (node (ref "R65") (pin "1") (pintype "passive"))
      (node (ref "VT13") (pin "2") (pinfunction "G2_2") (pintype "passive"))
    )
    (net (code "116") (name "Net-(VT14-D)") (class "Default")
      (node (ref "R65") (pin "2") (pintype "passive"))
      (node (ref "VT14") (pin "3") (pinfunction "D_3") (pintype "passive"))
    )
    (net (code "117") (name "Net-(VT15-D)") (class "Default")
      (node (ref "R69") (pin "2") (pintype "passive"))
      (node (ref "VT15") (pin "3") (pinfunction "D_3") (pintype "passive"))
    )
    (net (code "118") (name "Net-(VT16B-G2)") (class "Default")
      (node (ref "R72") (pin "1") (pintype "passive"))
      (node (ref "R73") (pin "1") (pintype "passive"))
      (node (ref "VT16") (pin "2") (pinfunction "G2_2") (pintype "passive"))
    )
    (net (code "119") (name "Net-(VT17-D)") (class "Default")
      (node (ref "R73") (pin "2") (pintype "passive"))
      (node (ref "VT17") (pin "3") (pinfunction "D_3") (pintype "passive"))
    )
    (net (code "120") (name "SGND") (class "Default")
      (node (ref "C23") (pin "2") (pintype "passive"))
      (node (ref "C24") (pin "2") (pintype "passive"))
      (node (ref "DD5") (pin "29") (pinfunction "GND_29") (pintype "passive"))
      (node (ref "DD5") (pin "3") (pinfunction "GND_3") (pintype "passive"))
      (node (ref "PC8") (pin "3") (pintype "passive"))
      (node (ref "R54") (pin "1") (pintype "passive"))
      (node (ref "VD4") (pin "1") (pinfunction "1_1") (pintype "passive"))
      (node (ref "VD5") (pin "1") (pinfunction "1_1") (pintype "passive"))
      (node (ref "VD6") (pin "1") (pinfunction "1_1") (pintype "passive"))
      (node (ref "VD7") (pin "1") (pinfunction "1_1") (pintype "passive"))
      (node (ref "XP8") (pin "GND") (pinfunction "GND_GND") (pintype "passive"))
      (node (ref "XP8") (pin "GND2") (pinfunction "GND2_GND2") (pintype "passive"))
      (node (ref "XP9") (pin "2") (pinfunction "2_2") (pintype "passive"))
    )
    (net (code "121") (name "unconnected-(DD1-PA11-Pad32)") (class "Default")
      (node (ref "DD1") (pin "32") (pinfunction "PA11_32") (pintype "passive"))
    )
    (net (code "122") (name "unconnected-(DD1-PA15-Pad38)") (class "Default")
      (node (ref "DD1") (pin "38") (pinfunction "PA15_38") (pintype "passive"))
    )
    (net (code "123") (name "unconnected-(DD1-PB2-Pad20)") (class "Default")
      (node (ref "DD1") (pin "20") (pinfunction "PB2_20") (pintype "passive"))
    )
    (net (code "124") (name "unconnected-(DD1-PB8-Pad45)") (class "Default")
      (node (ref "DD1") (pin "45") (pinfunction "PB8_45") (pintype "passive"))
    )
    (net (code "125") (name "unconnected-(DD1-PB9-Pad46)") (class "Default")
      (node (ref "DD1") (pin "46") (pinfunction "PB9_46") (pintype "passive"))
    )
    (net (code "126") (name "unconnected-(DD1-PF0-OSC_IN-Pad5)") (class "Default")
      (node (ref "DD1") (pin "5") (pinfunction "PF0-OSC_IN_5") (pintype "passive"))
    )
    (net (code "127") (name "unconnected-(DD1-PF1-OSC_OUT-Pad6)") (class "Default")
      (node (ref "DD1") (pin "6") (pinfunction "PF1-OSC_OUT_6") (pintype "passive"))
    )
    (net (code "128") (name "unconnected-(DD5-CTS-Pad23)") (class "Default")
      (node (ref "DD5") (pin "23") (pinfunction "CTS_23") (pintype "input"))
    )
    (net (code "129") (name "unconnected-(DD5-DCD-Pad1)") (class "Default")
      (node (ref "DD5") (pin "1") (pinfunction "DCD_1") (pintype "input"))
    )
    (net (code "130") (name "unconnected-(DD5-DSR-Pad27)") (class "Default")
      (node (ref "DD5") (pin "27") (pinfunction "DSR_27") (pintype "input"))
    )
    (net (code "131") (name "unconnected-(DD5-DTR-Pad28)") (class "Default")
      (node (ref "DD5") (pin "28") (pinfunction "DTR_28") (pintype "output"))
    )
    (net (code "132") (name "unconnected-(DD5-NC-Pad10)") (class "Default")
      (node (ref "DD5") (pin "10") (pinfunction "NC_10") (pintype "passive"))
    )
    (net (code "133") (name "unconnected-(DD5-NC-Pad13)") (class "Default")
      (node (ref "DD5") (pin "13") (pinfunction "NC_13") (pintype "passive"))
    )
    (net (code "134") (name "unconnected-(DD5-NC-Pad14)") (class "Default")
      (node (ref "DD5") (pin "14") (pinfunction "NC_14") (pintype "passive"))
    )
    (net (code "135") (name "unconnected-(DD5-NC-Pad15)") (class "Default")
      (node (ref "DD5") (pin "15") (pinfunction "NC_15") (pintype "passive"))
    )
    (net (code "136") (name "unconnected-(DD5-NC-Pad16)") (class "Default")
      (node (ref "DD5") (pin "16") (pinfunction "NC_16") (pintype "passive"))
    )
    (net (code "137") (name "unconnected-(DD5-NC-Pad17)") (class "Default")
      (node (ref "DD5") (pin "17") (pinfunction "NC_17") (pintype "passive"))
    )
    (net (code "138") (name "unconnected-(DD5-NC-Pad19)") (class "Default")
      (node (ref "DD5") (pin "19") (pinfunction "NC_19") (pintype "passive"))
    )
    (net (code "139") (name "unconnected-(DD5-NC-Pad20)") (class "Default")
      (node (ref "DD5") (pin "20") (pinfunction "NC_20") (pintype "passive"))
    )
    (net (code "140") (name "unconnected-(DD5-NC-Pad21)") (class "Default")
      (node (ref "DD5") (pin "21") (pinfunction "NC_21") (pintype "passive"))
    )
    (net (code "141") (name "unconnected-(DD5-NC-Pad22)") (class "Default")
      (node (ref "DD5") (pin "22") (pinfunction "NC_22") (pintype "passive"))
    )
    (net (code "142") (name "unconnected-(DD5-NC{slash}VPP-Pad18)") (class "Default")
      (node (ref "DD5") (pin "18") (pinfunction "NC/VPP_18") (pintype "passive"))
    )
    (net (code "143") (name "unconnected-(DD5-RI-Pad2)") (class "Default")
      (node (ref "DD5") (pin "2") (pinfunction "RI_2") (pintype "input"))
    )
    (net (code "144") (name "unconnected-(DD5-RST-Pad9)") (class "Default")
      (node (ref "DD5") (pin "9") (pinfunction "RST_9") (pintype "passive"))
    )
    (net (code "145") (name "unconnected-(DD5-RTS-Pad24)") (class "Default")
      (node (ref "DD5") (pin "24") (pinfunction "RTS_24") (pintype "output"))
    )
    (net (code "146") (name "unconnected-(DD5-SUSPEND#-Pad11)") (class "Default")
      (node (ref "DD5") (pin "11") (pinfunction "SUSPEND#_11") (pintype "output"))
    )
    (net (code "147") (name "unconnected-(DD5-SUSPEND-Pad12)") (class "Default")
      (node (ref "DD5") (pin "12") (pinfunction "SUSPEND_12") (pintype "output"))
    )
    (net (code "148") (name "unconnected-(XP8-PadID)") (class "Default")
      (node (ref "XP8") (pin "ID") (pinfunction "ID_ID") (pintype "passive"))
    )
  )
)
